# ClickMeter_BlackBox_v1_9_4.net
KiCad netlist of a schematic drawn in EAGLE
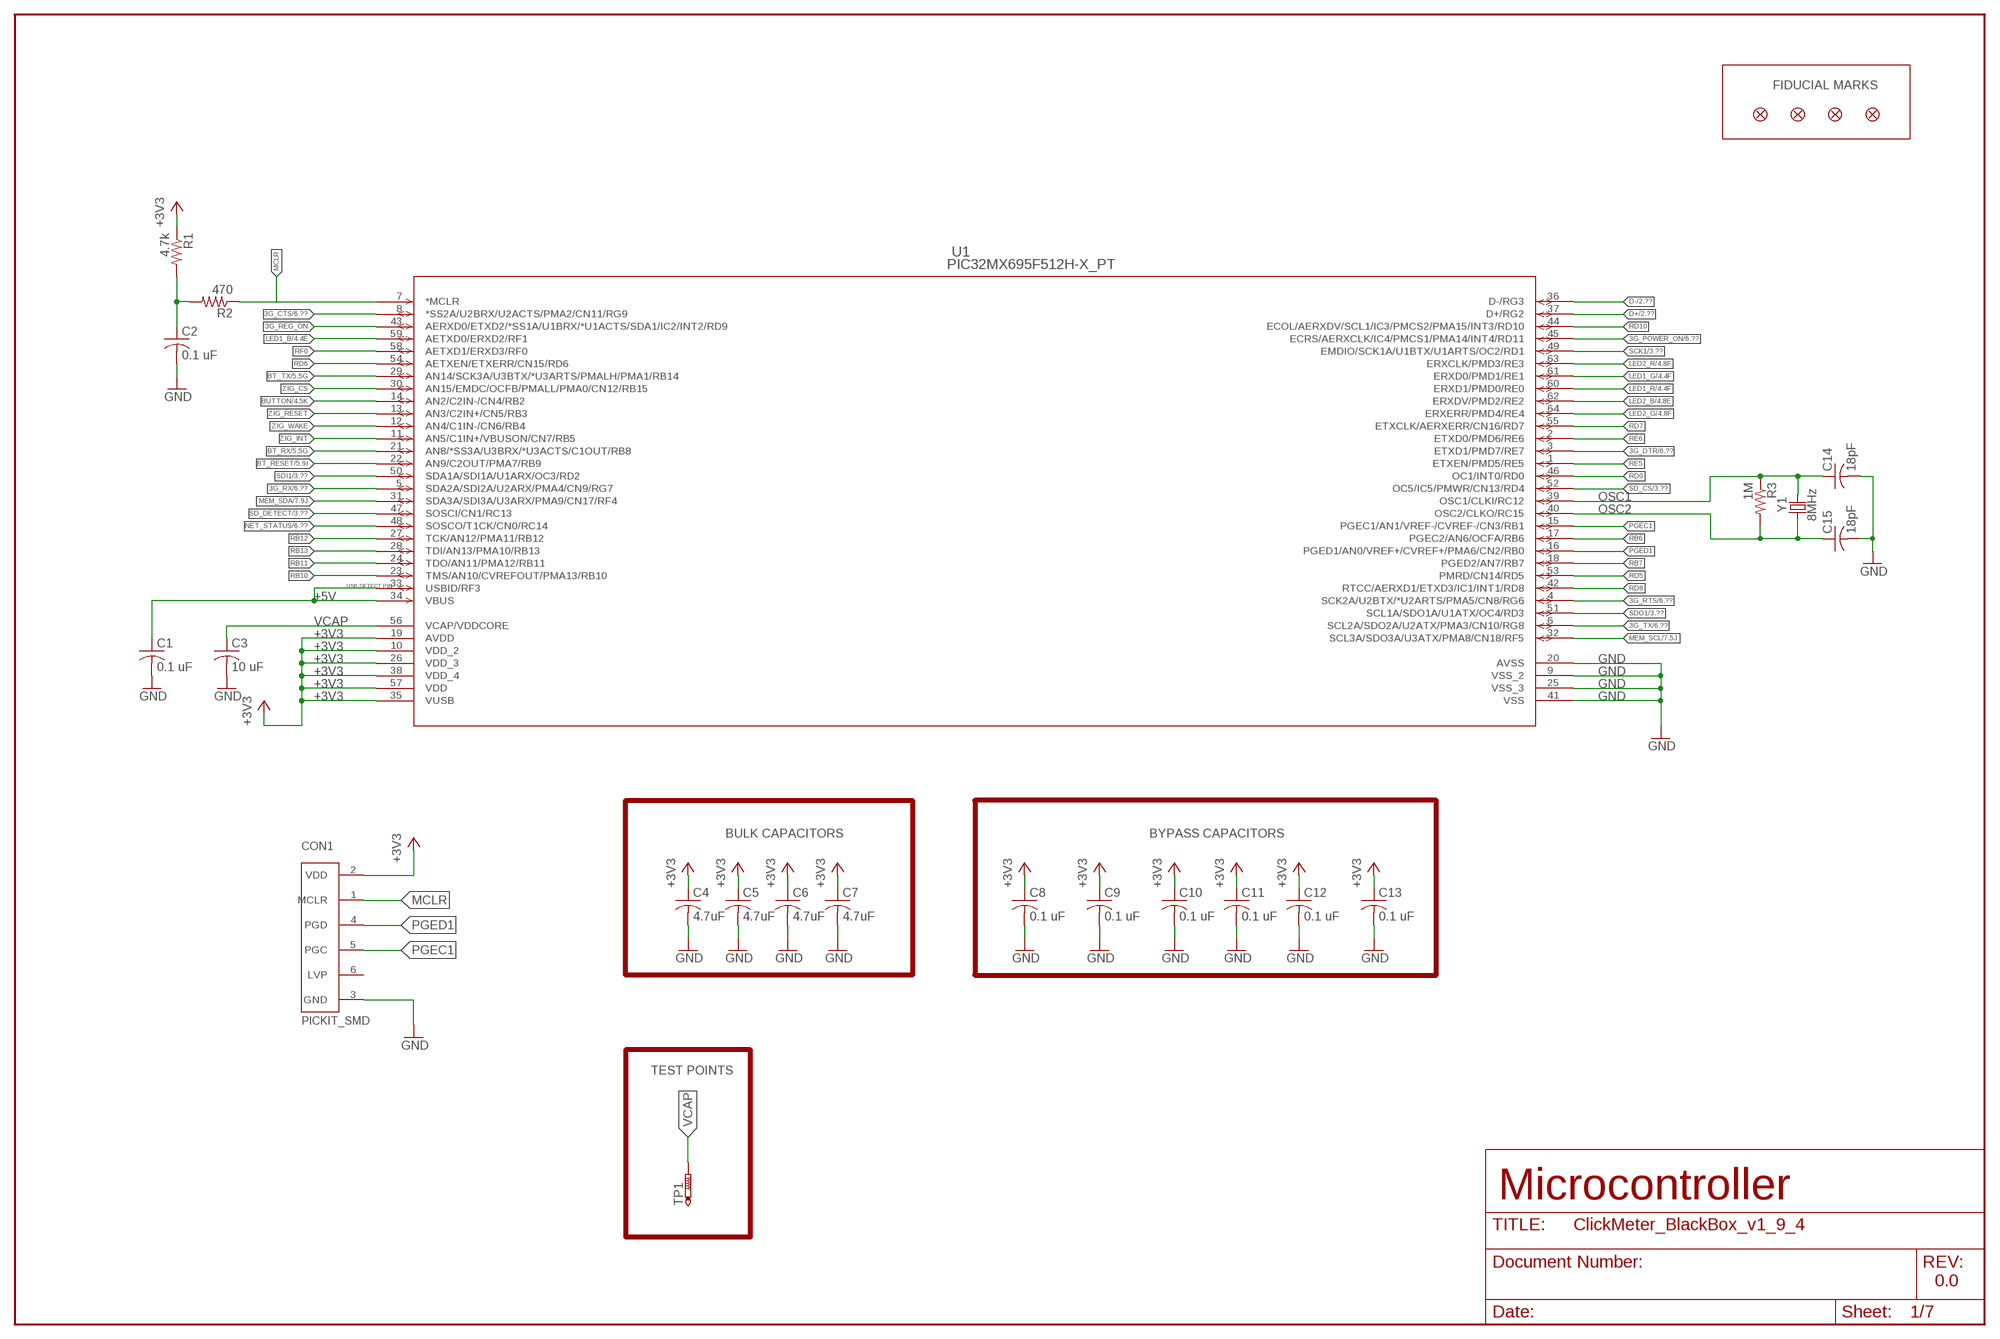
[diagram p0: schematic, sheet 1]
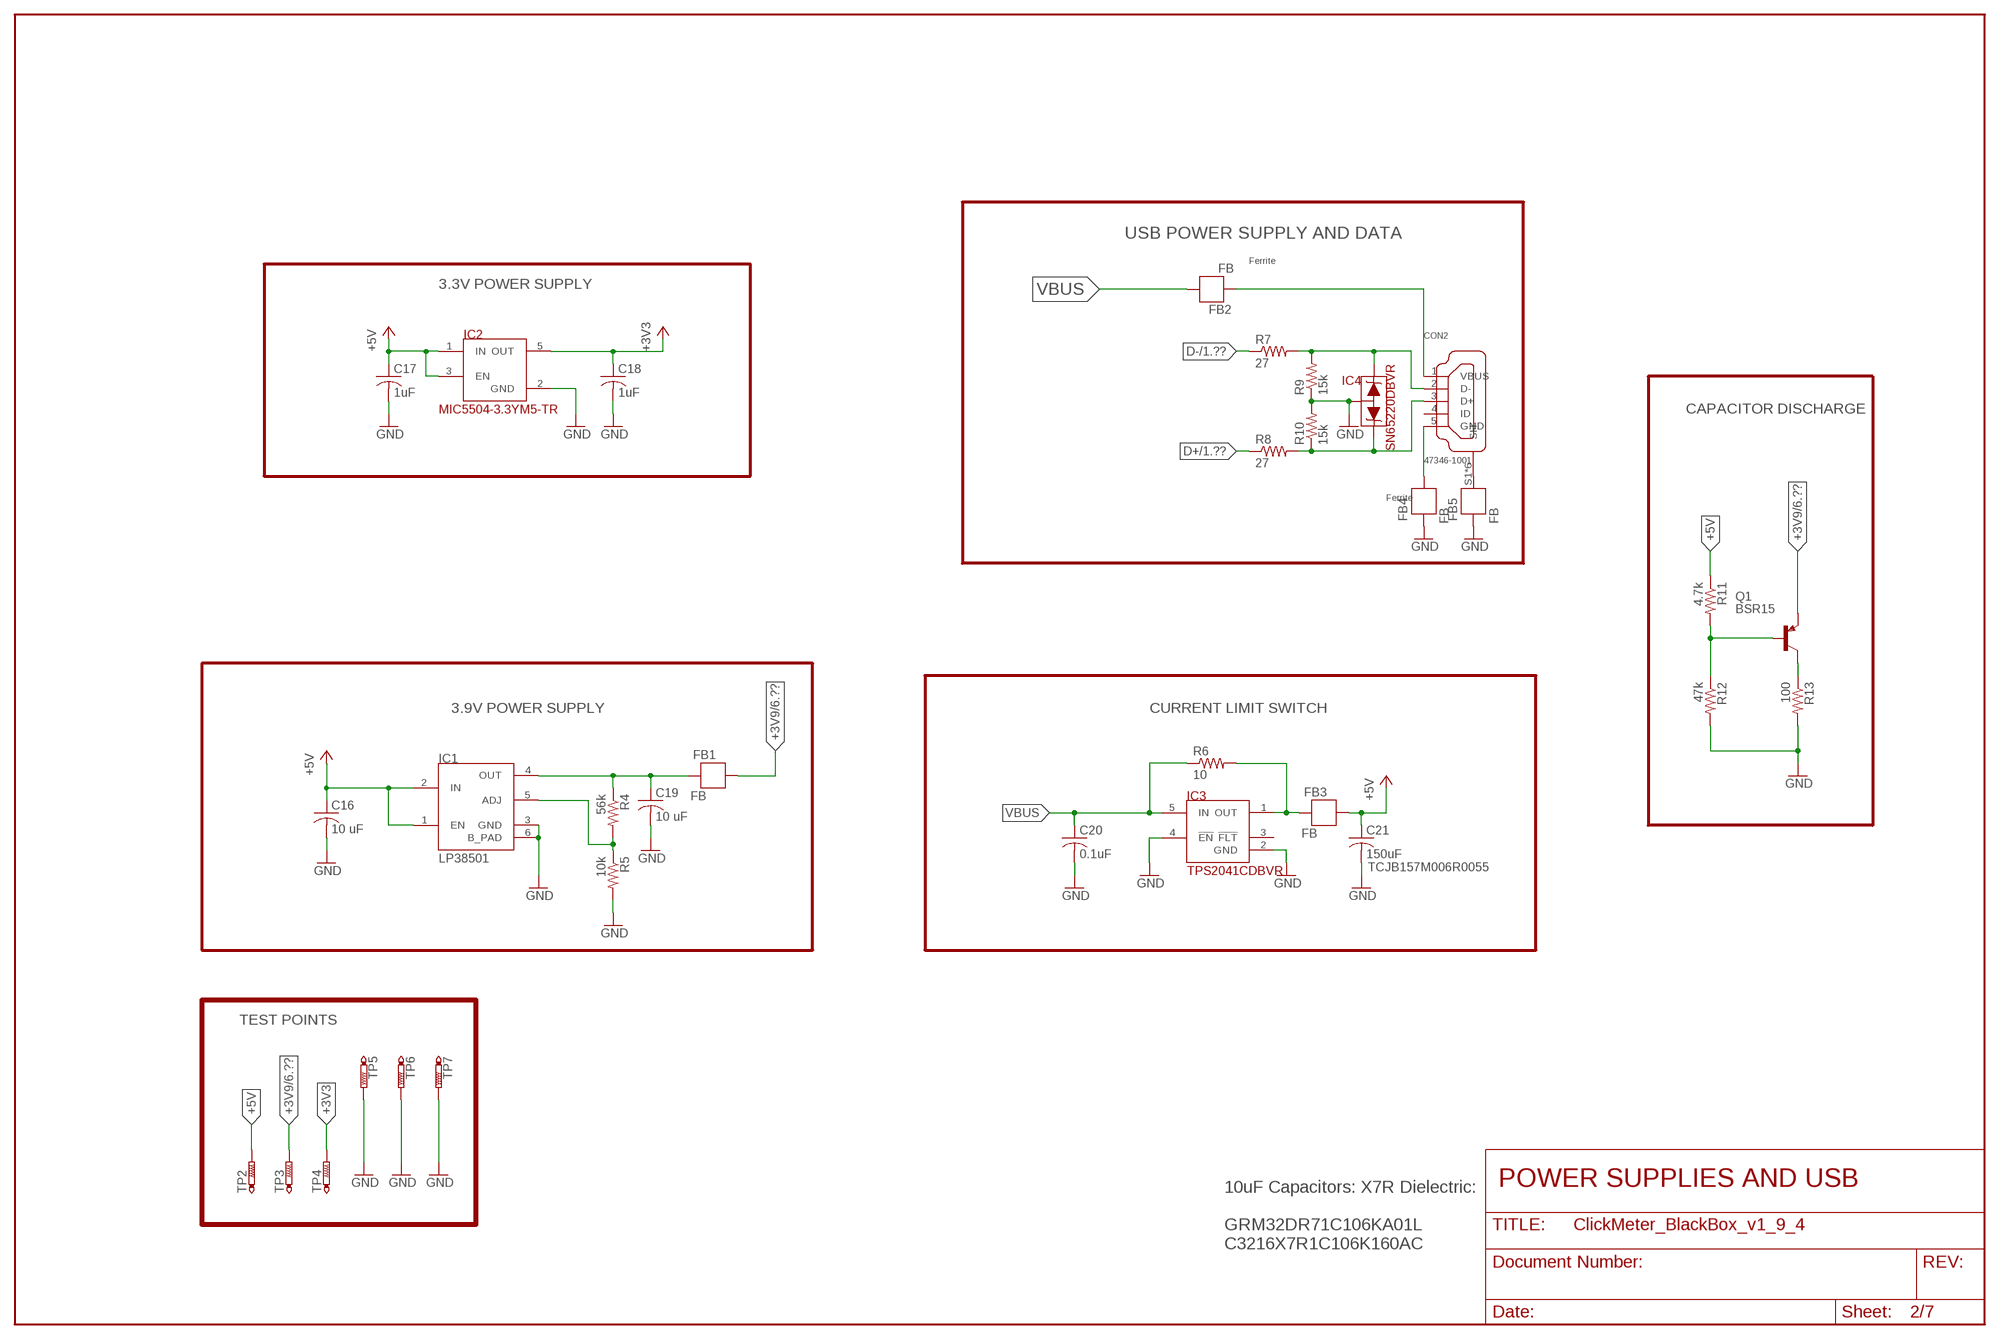
[diagram p1: schematic, sheet 2]
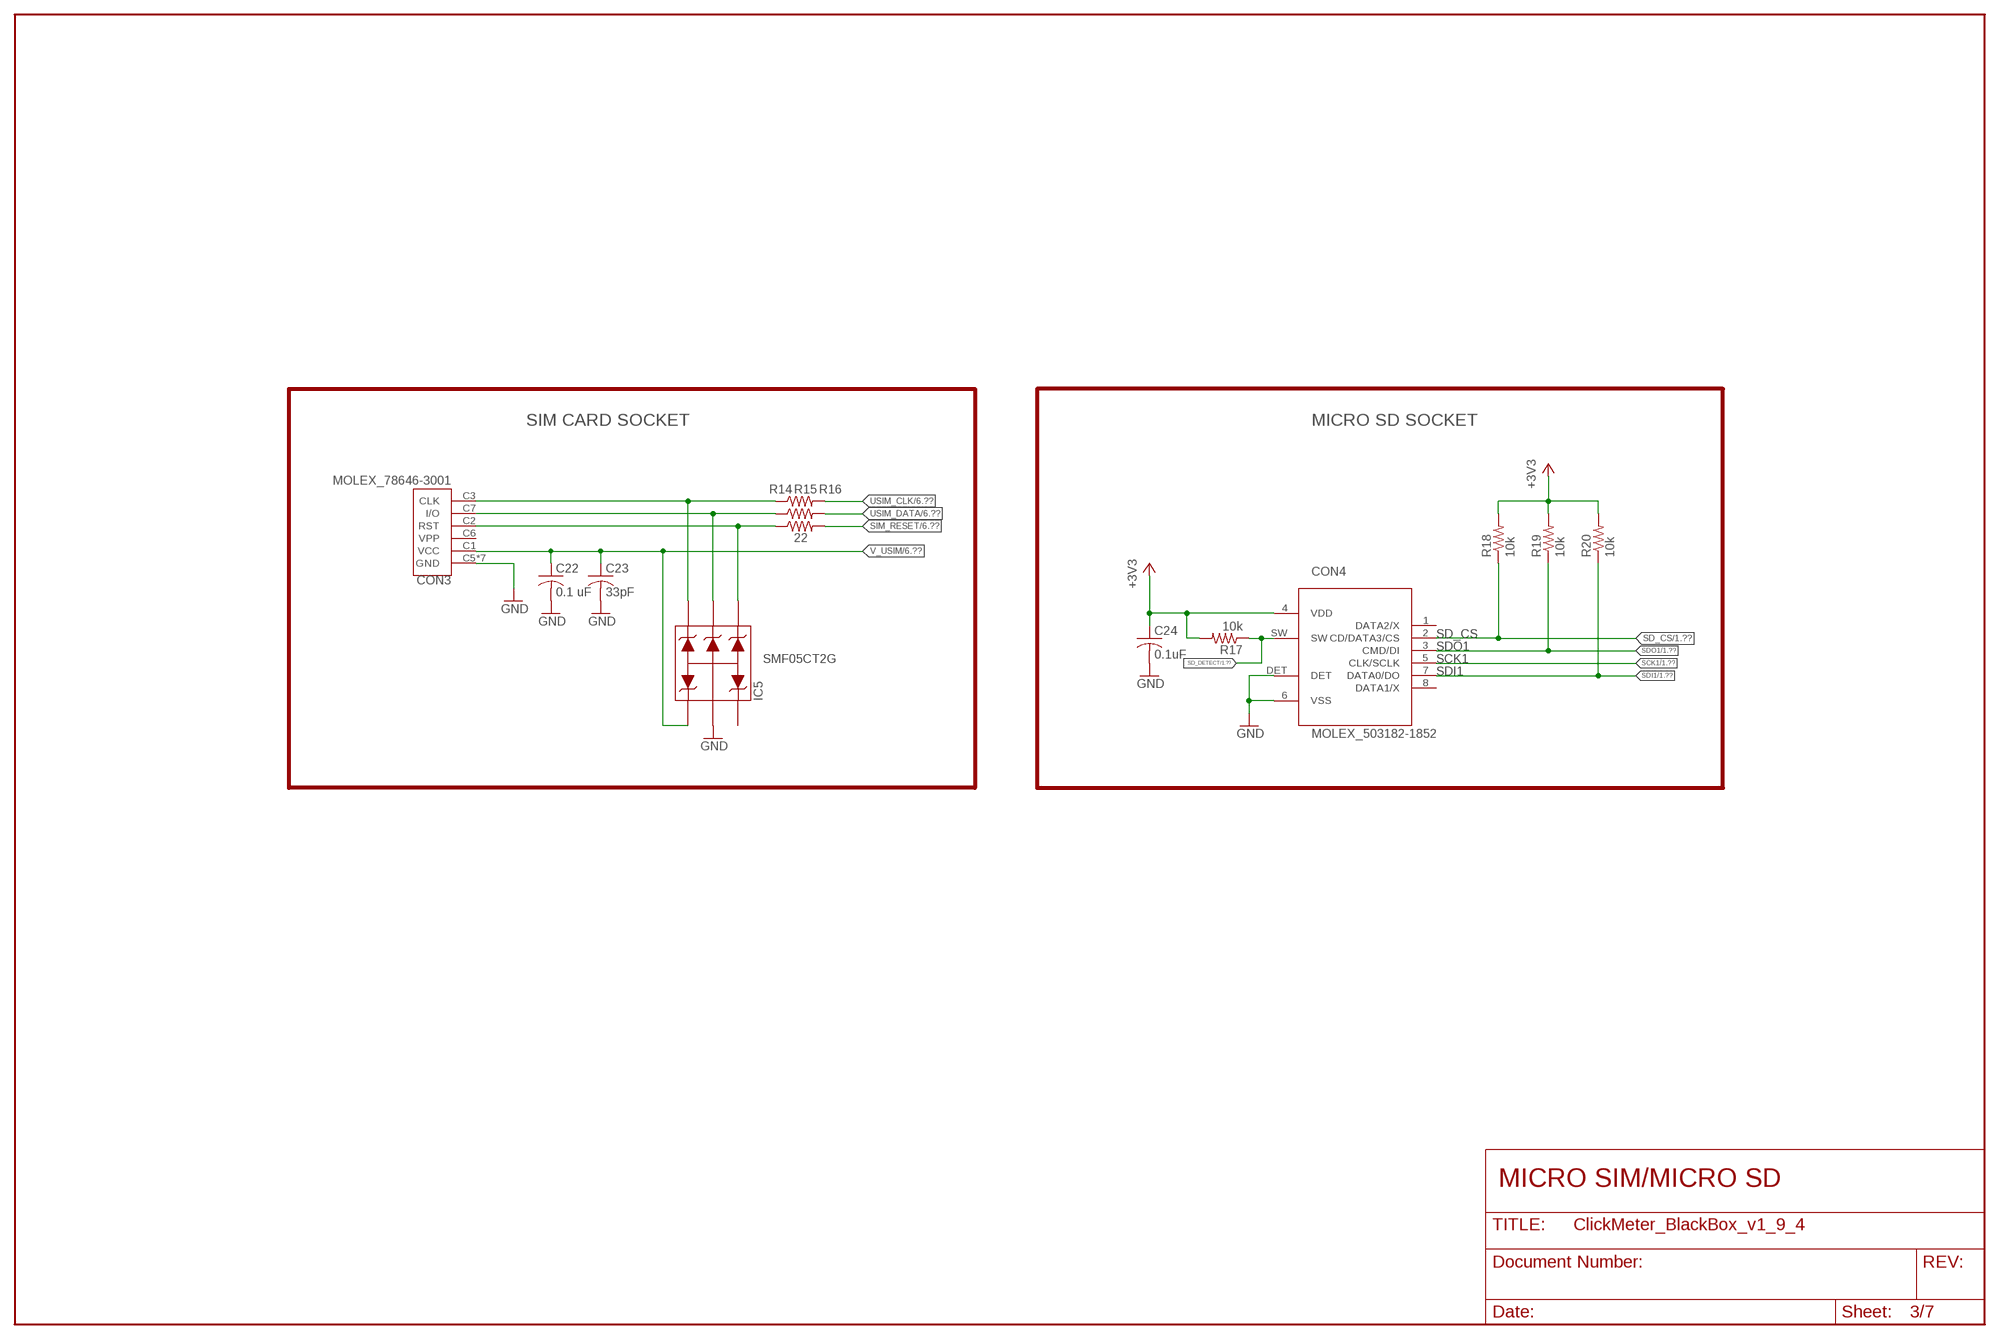
[diagram p2: schematic, sheet 3]
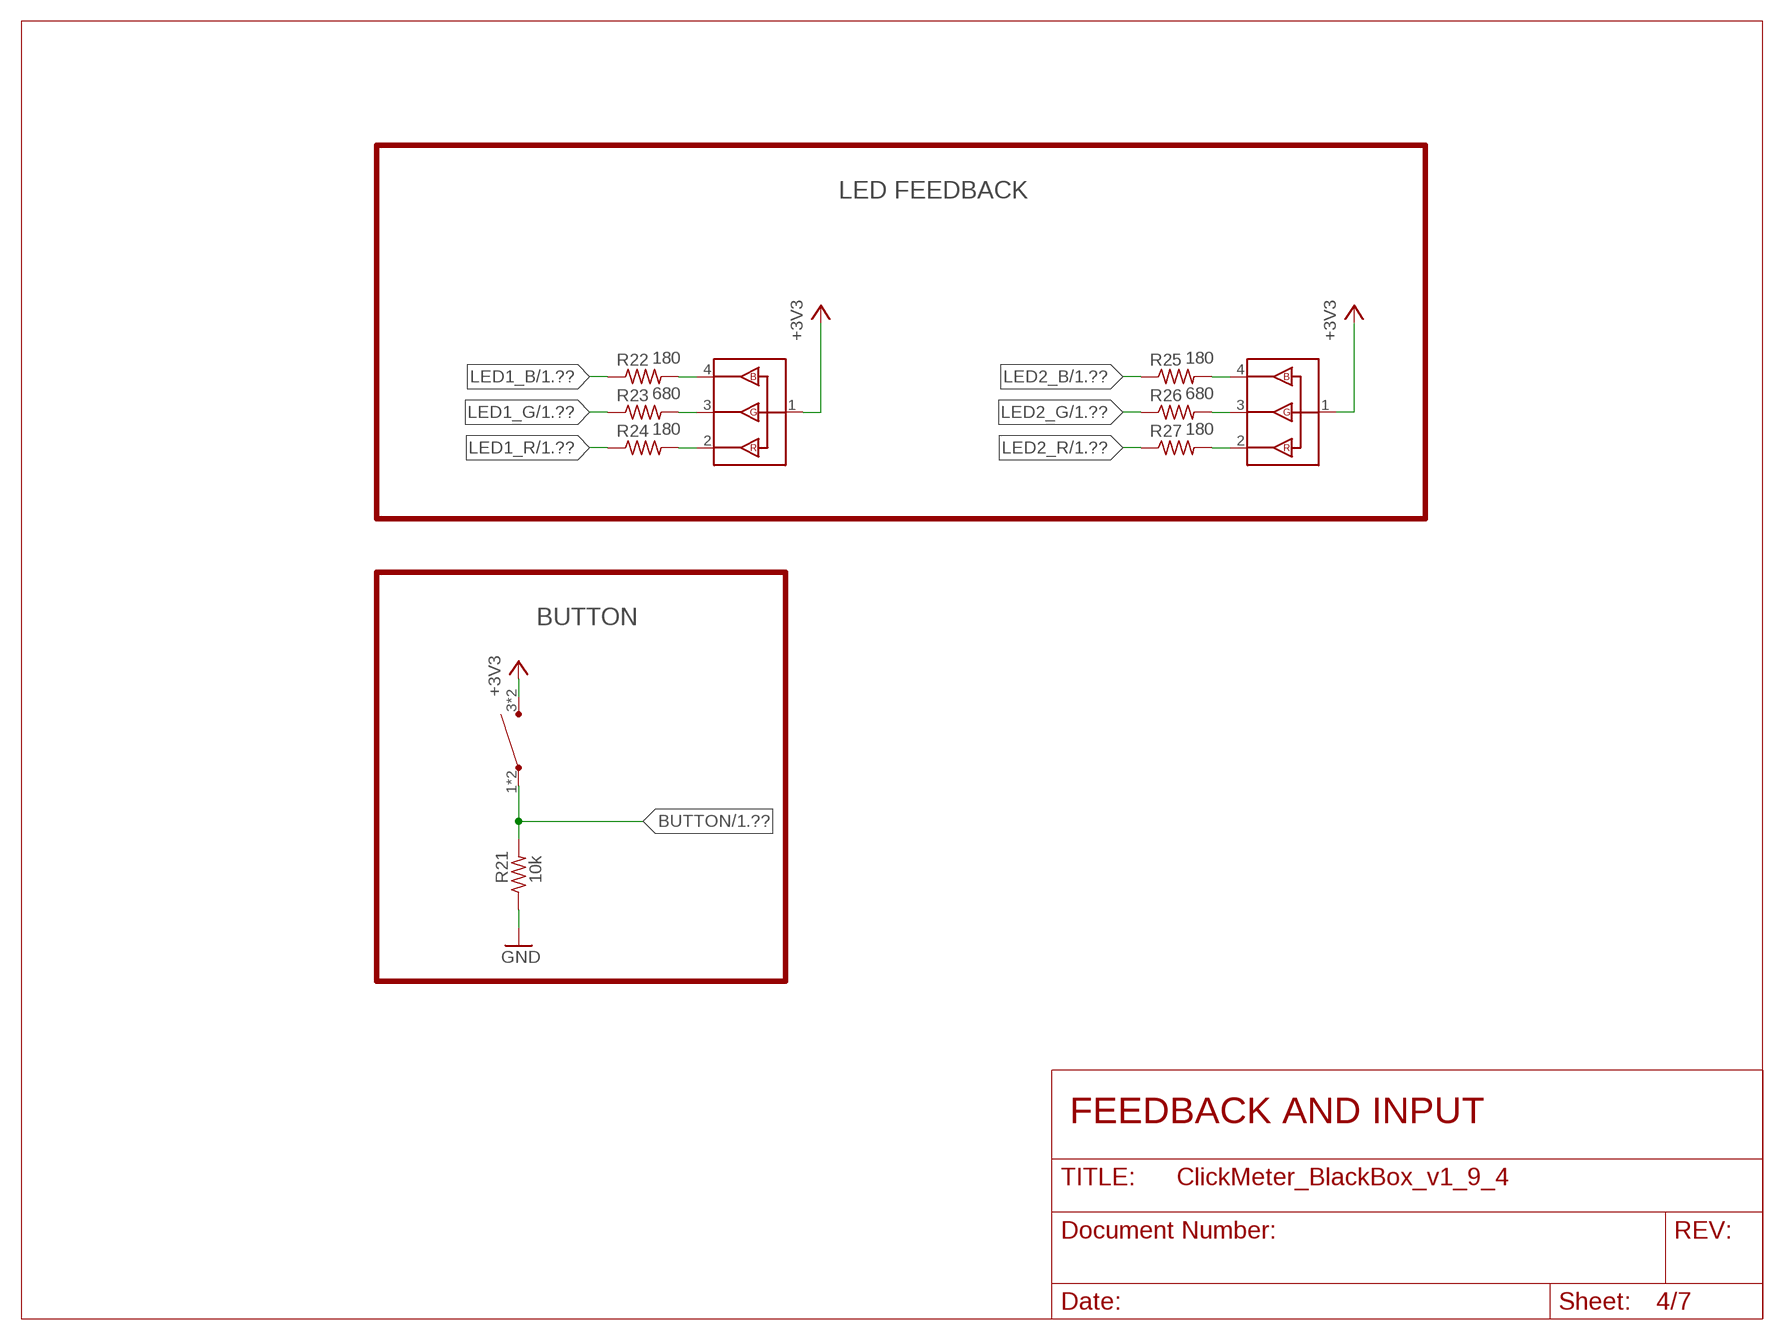
[diagram p3: schematic, sheet 4]
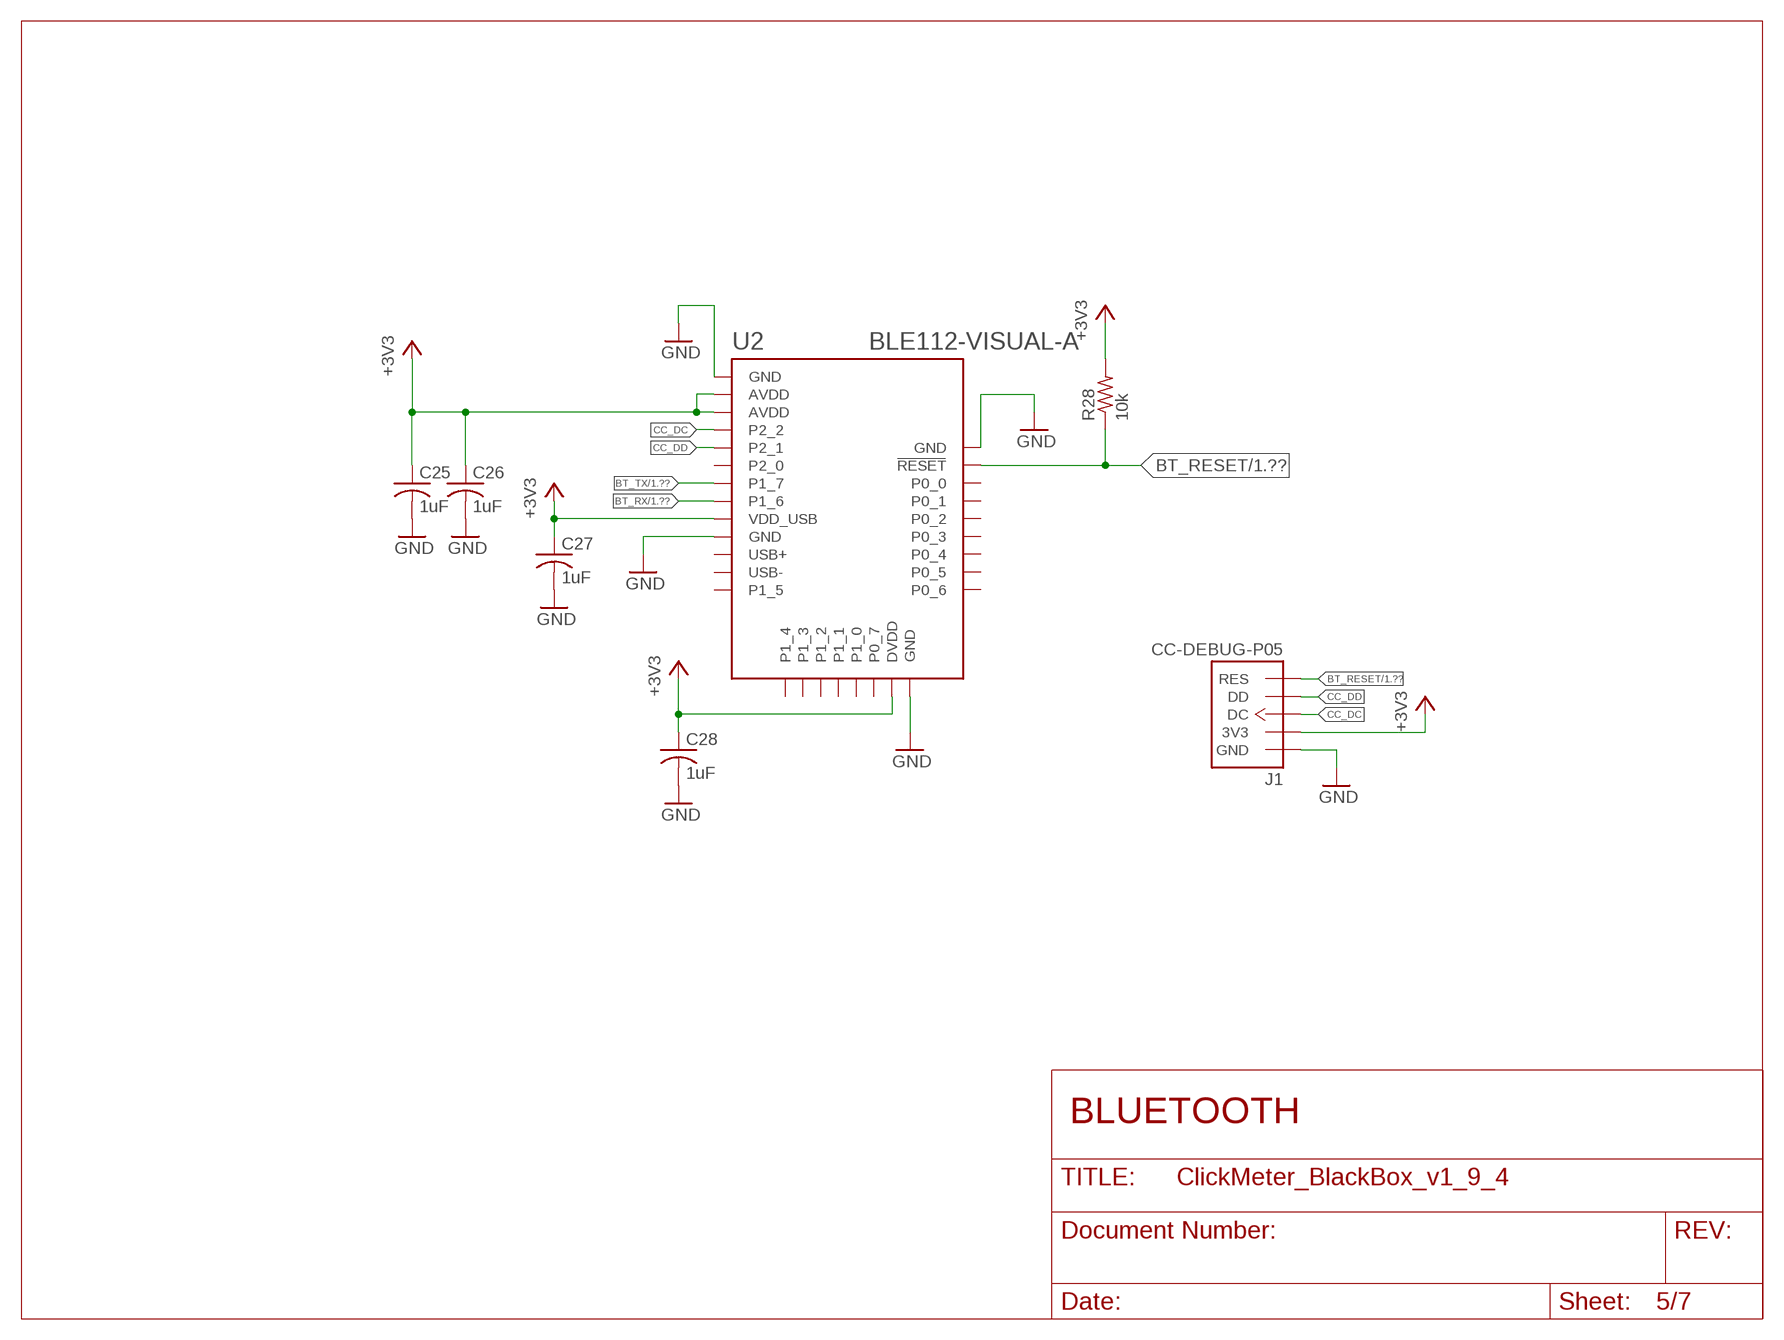
[diagram p4: schematic, sheet 5]
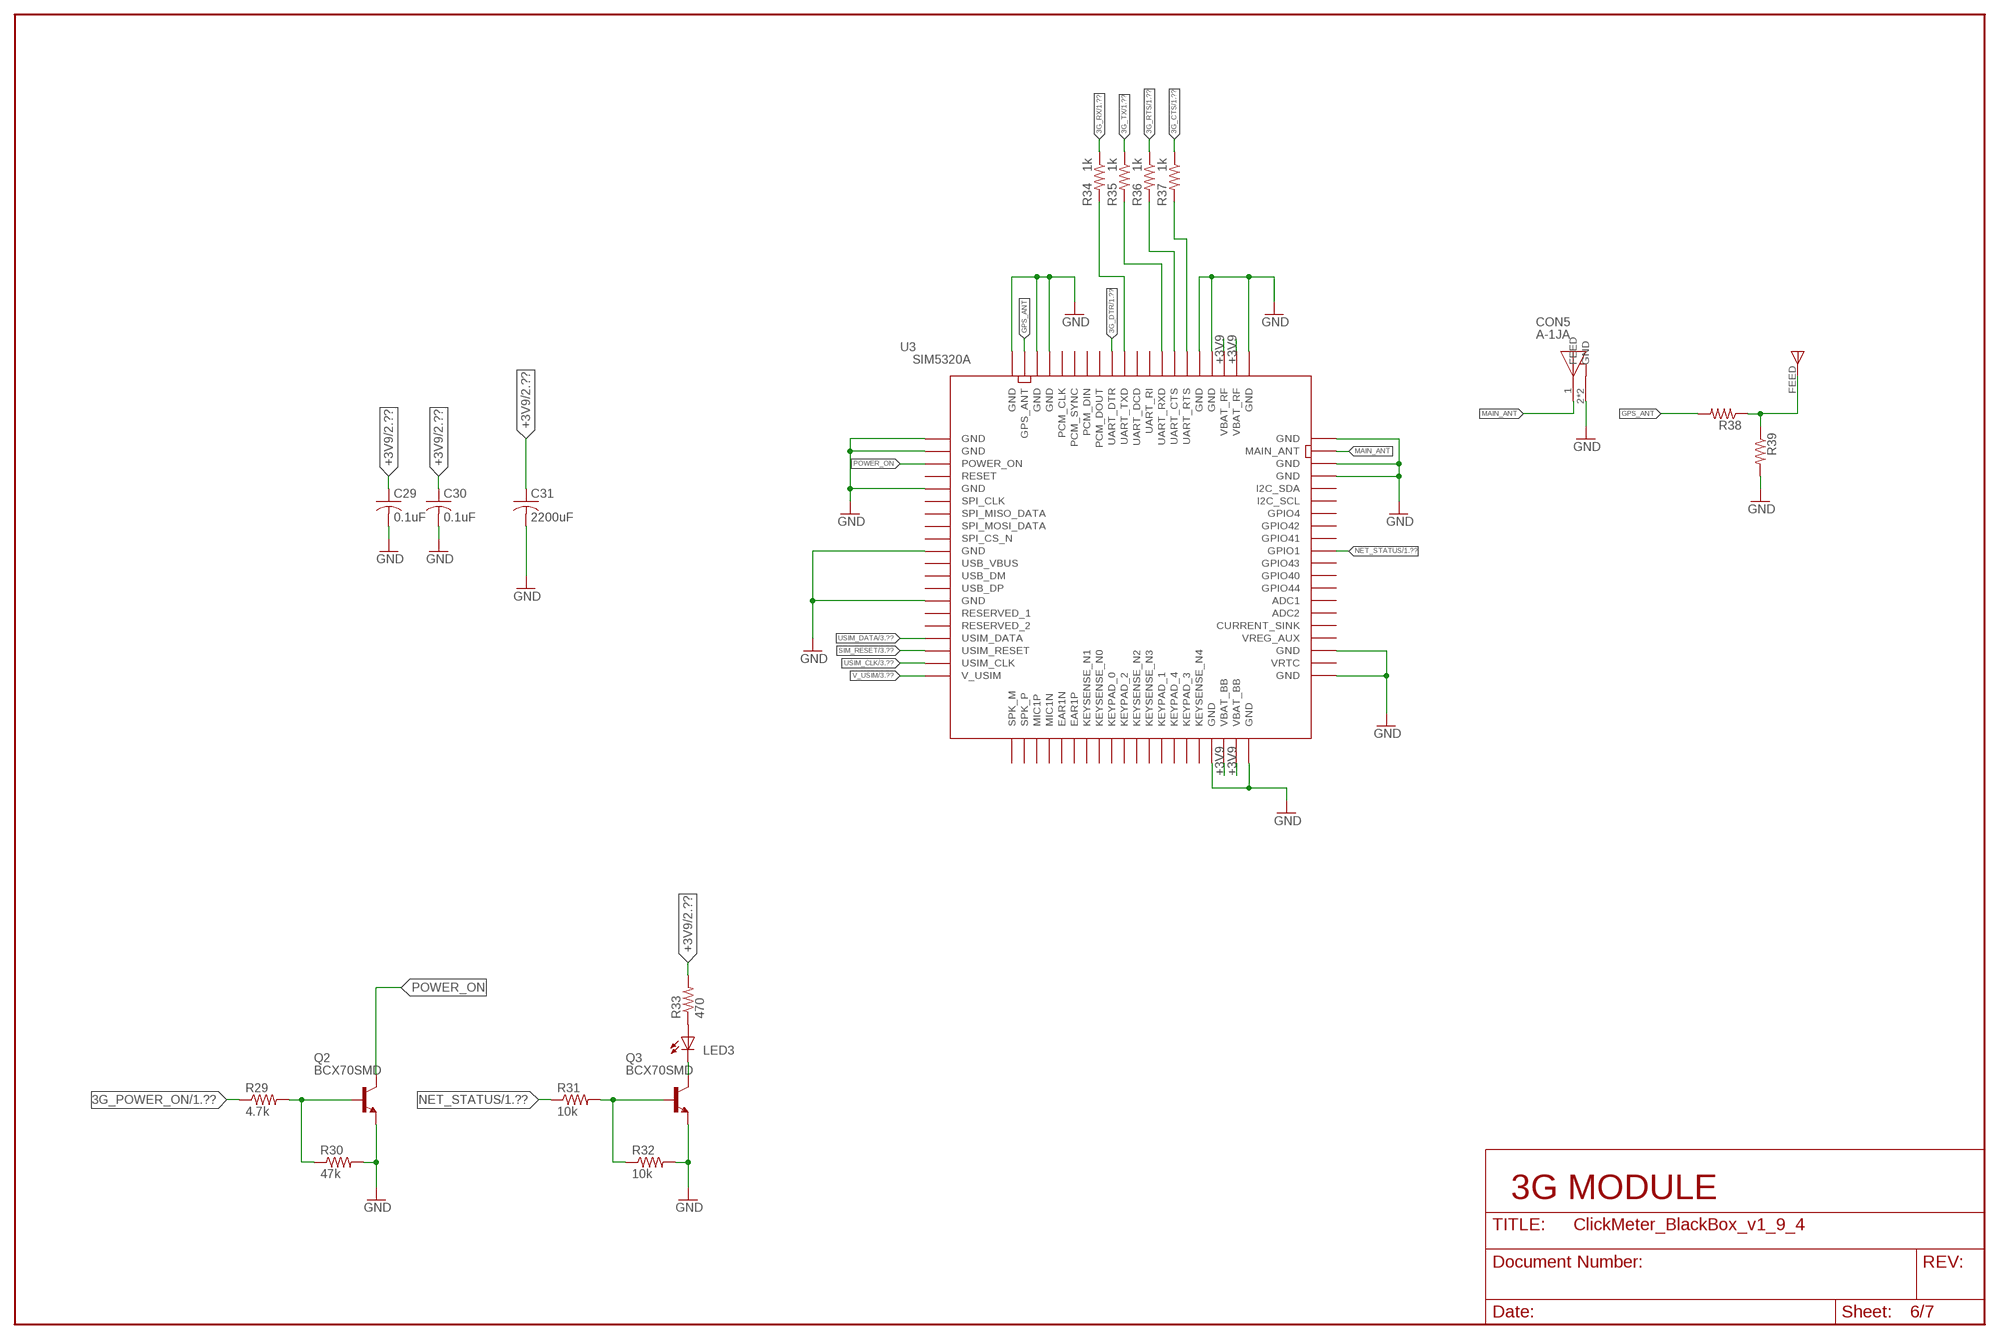
[diagram p5: schematic, sheet 6]
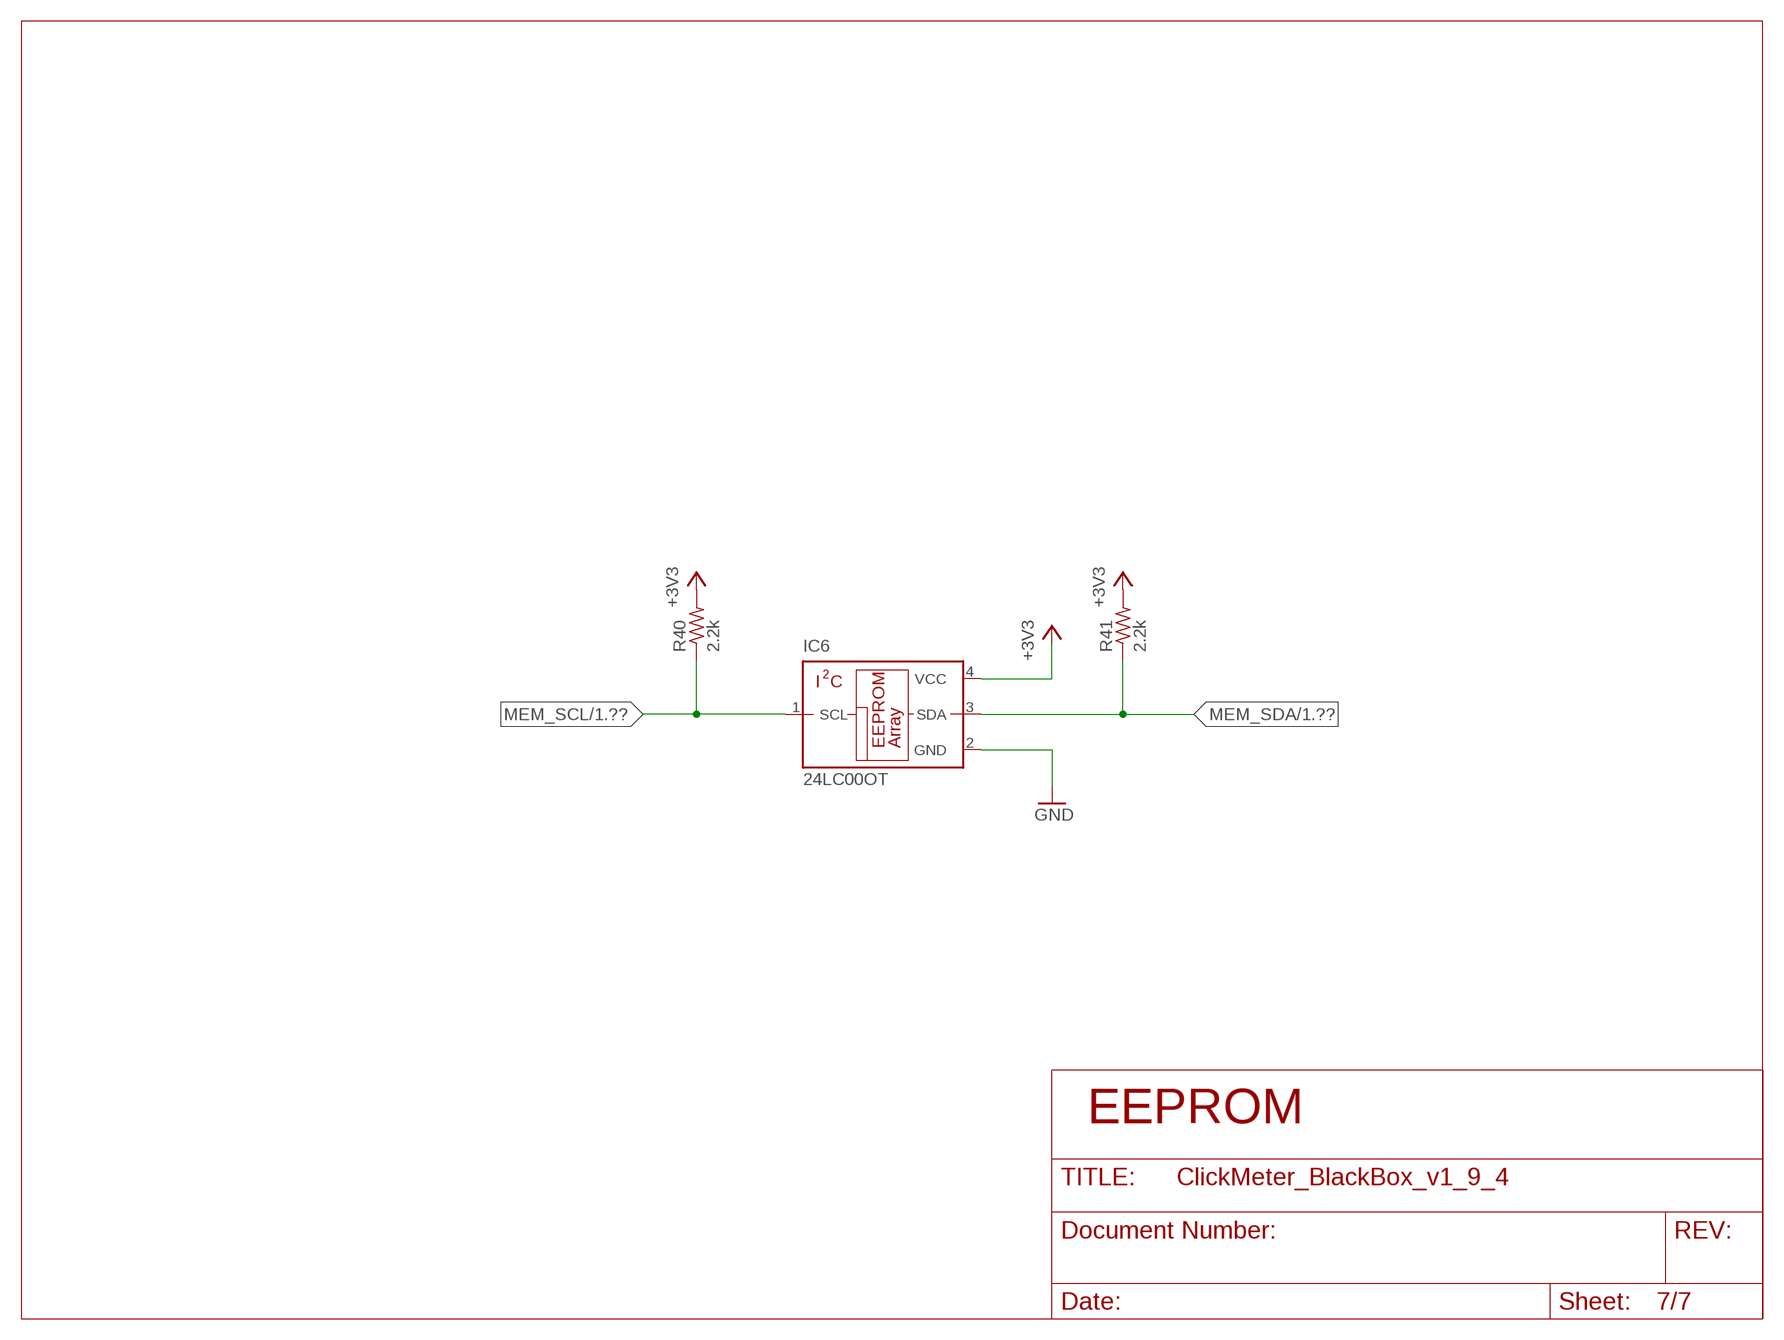
[diagram p6: schematic, sheet 7]

(export (version "E")
  (design (tool "Eeschema 10.0.6"))
  (components
    (comp (ref "C25")
      (value "1uF")
      (footprint "eagle-import:C0603")
      (libsource (lib "eagle-import") (part "C-USC0603"))
    )
    (comp (ref "C26")
      (value "1uF")
      (footprint "eagle-import:C0603")
      (libsource (lib "eagle-import") (part "C-USC0603"))
    )
    (comp (ref "C27")
      (value "1uF")
      (footprint "eagle-import:C0603")
      (libsource (lib "eagle-import") (part "C-USC0603"))
    )
    (comp (ref "C28")
      (value "1uF")
      (footprint "eagle-import:C0603")
      (libsource (lib "eagle-import") (part "C-USC0603"))
    )
    (comp (ref "J1")
      (value "CC-DEBUG-P05")
      (footprint "eagle-import:CC-P05")
      (libsource (lib "eagle-import") (part "CC-DEBUG-P05"))
    )
    (comp (ref "R28")
      (value "10k")
      (footprint "eagle-import:R0603")
      (libsource (lib "eagle-import") (part "R-US_R0603"))
    )
    (comp (ref "U2")
      (value "BLE112-VISUAL-A")
      (footprint "eagle-import:BLE112-A")
      (libsource (lib "eagle-import") (part "BLE112-VISUAL-A"))
    )
    (comp (ref "C16")
      (value "10 uF")
      (footprint "eagle-import:C0805")
      (libsource (lib "eagle-import") (part "C-USC0805"))
    )
    (comp (ref "C17")
      (value "1uF")
      (footprint "eagle-import:C0603")
      (libsource (lib "eagle-import") (part "C-USC0603"))
    )
    (comp (ref "C18")
      (value "1uF")
      (footprint "eagle-import:C0603")
      (libsource (lib "eagle-import") (part "C-USC0603"))
    )
    (comp (ref "C19")
      (value "10 uF")
      (footprint "eagle-import:C0805")
      (libsource (lib "eagle-import") (part "C-USC0805"))
    )
    (comp (ref "C20")
      (value "0.1uF")
      (footprint "eagle-import:C0603")
      (libsource (lib "eagle-import") (part "C-USC0603"))
    )
    (comp (ref "C21")
      (value "150uF")
      (footprint "eagle-import:C1210")
      (libsource (lib "eagle-import") (part "C-USC1210"))
    )
    (comp (ref "CON2")
      (value "47346-1001")
      (footprint "eagle-import:47346-1001")
      (libsource (lib "eagle-import") (part "47346-1001"))
    )
    (comp (ref "FB1")
      (value "FB")
      (footprint "eagle-import:0603")
      (libsource (lib "eagle-import") (part "FB"))
    )
    (comp (ref "FB2")
      (value "FB")
      (footprint "eagle-import:0603")
      (libsource (lib "eagle-import") (part "FB"))
    )
    (comp (ref "FB3")
      (value "FB")
      (footprint "eagle-import:0603")
      (libsource (lib "eagle-import") (part "FB"))
    )
    (comp (ref "FB4")
      (value "FB")
      (footprint "eagle-import:0603")
      (libsource (lib "eagle-import") (part "FB"))
    )
    (comp (ref "FB5")
      (value "FB")
      (footprint "eagle-import:0603")
      (libsource (lib "eagle-import") (part "FB"))
    )
    (comp (ref "IC1")
      (value "LP38501")
      (footprint "eagle-import:TO-263-5")
      (libsource (lib "eagle-import") (part "LP38501"))
    )
    (comp (ref "IC2")
      (value "MIC5504-3.3YM5-TR")
      (footprint "eagle-import:SOT-23-5")
      (libsource (lib "eagle-import") (part "MIC5504-3.3YM5-TR"))
    )
    (comp (ref "IC3")
      (value "TPS2041CDBVR")
      (footprint "eagle-import:SOT-23-5")
      (libsource (lib "eagle-import") (part "TPS2041CDBVR"))
    )
    (comp (ref "IC4")
      (value "SN65220DBVR")
      (footprint "eagle-import:SOT-23-6")
      (libsource (lib "eagle-import") (part "SN65220DBVR"))
    )
    (comp (ref "Q1")
      (value "BSR15")
      (footprint "eagle-import:SOT23")
      (libsource (lib "eagle-import") (part "BSR15"))
    )
    (comp (ref "R4")
      (value "56k")
      (footprint "eagle-import:R0603")
      (libsource (lib "eagle-import") (part "R-US_R0603"))
    )
    (comp (ref "R5")
      (value "10k")
      (footprint "eagle-import:R0603")
      (libsource (lib "eagle-import") (part "R-US_R0603"))
    )
    (comp (ref "R6")
      (value "10")
      (footprint "eagle-import:R2010")
      (libsource (lib "eagle-import") (part "R-US_R2010"))
    )
    (comp (ref "R7")
      (value "27")
      (footprint "eagle-import:R0603")
      (libsource (lib "eagle-import") (part "R-US_R0603"))
    )
    (comp (ref "R8")
      (value "27")
      (footprint "eagle-import:R0603")
      (libsource (lib "eagle-import") (part "R-US_R0603"))
    )
    (comp (ref "R9")
      (value "15k")
      (footprint "eagle-import:R0603")
      (libsource (lib "eagle-import") (part "R-US_R0603"))
    )
    (comp (ref "R10")
      (value "15k")
      (footprint "eagle-import:R0603")
      (libsource (lib "eagle-import") (part "R-US_R0603"))
    )
    (comp (ref "R11")
      (value "4.7k")
      (footprint "eagle-import:R0603")
      (libsource (lib "eagle-import") (part "R-US_R0603"))
    )
    (comp (ref "R12")
      (value "47k")
      (footprint "eagle-import:R0603")
      (libsource (lib "eagle-import") (part "R-US_R0603"))
    )
    (comp (ref "R13")
      (value "100")
      (footprint "eagle-import:R0603")
      (libsource (lib "eagle-import") (part "R-US_R0603"))
    )
    (comp (ref "TP2")
      (value "PTR1B1,27")
      (footprint "eagle-import:B1,27")
      (libsource (lib "eagle-import") (part "PTR1B1,27"))
    )
    (comp (ref "TP3")
      (value "PTR1B1,27")
      (footprint "eagle-import:B1,27")
      (libsource (lib "eagle-import") (part "PTR1B1,27"))
    )
    (comp (ref "TP4")
      (value "PTR1B1,27")
      (footprint "eagle-import:B1,27")
      (libsource (lib "eagle-import") (part "PTR1B1,27"))
    )
    (comp (ref "TP5")
      (value "PTR1B1,27")
      (footprint "eagle-import:B1,27")
      (libsource (lib "eagle-import") (part "PTR1B1,27"))
    )
    (comp (ref "TP6")
      (value "PTR1B1,27")
      (footprint "eagle-import:B1,27")
      (libsource (lib "eagle-import") (part "PTR1B1,27"))
    )
    (comp (ref "TP7")
      (value "PTR1B1,27")
      (footprint "eagle-import:B1,27")
      (libsource (lib "eagle-import") (part "PTR1B1,27"))
    )
    (comp (ref "ANT1")
      (value "1575AT43A0040E")
      (footprint "eagle-import:1575AT43A0040E")
      (libsource (lib "eagle-import") (part "1575AT43A0040E"))
    )
    (comp (ref "C29")
      (value "0.1uF")
      (footprint "eagle-import:C0603")
      (libsource (lib "eagle-import") (part "C-USC0603"))
    )
    (comp (ref "C30")
      (value "0.1uF")
      (footprint "eagle-import:C0603")
      (libsource (lib "eagle-import") (part "C-USC0603"))
    )
    (comp (ref "C31")
      (value "2200uF")
      (footprint "eagle-import:592D-2200")
      (libsource (lib "eagle-import") (part "C-USTANTALUM-592D"))
    )
    (comp (ref "CON5")
      (value "A-1JA")
      (footprint "eagle-import:A-1JA")
      (libsource (lib "eagle-import") (part "A-1JA"))
    )
    (comp (ref "LED3")
      (value "LED_ESML0603")
      (footprint "eagle-import:LED_SML0603")
      (libsource (lib "eagle-import") (part "LED_ESML0603"))
    )
    (comp (ref "Q2")
      (value "BCX70SMD")
      (footprint "eagle-import:SOT23")
      (libsource (lib "eagle-import") (part "BCX70SMD"))
    )
    (comp (ref "Q3")
      (value "BCX70SMD")
      (footprint "eagle-import:SOT23")
      (libsource (lib "eagle-import") (part "BCX70SMD"))
    )
    (comp (ref "R29")
      (value "4.7k")
      (footprint "eagle-import:R0603")
      (libsource (lib "eagle-import") (part "R-US_R0603"))
    )
    (comp (ref "R30")
      (value "47k")
      (footprint "eagle-import:R0603")
      (libsource (lib "eagle-import") (part "R-US_R0603"))
    )
    (comp (ref "R31")
      (value "10k")
      (footprint "eagle-import:R0603")
      (libsource (lib "eagle-import") (part "R-US_R0603"))
    )
    (comp (ref "R32")
      (value "10k")
      (footprint "eagle-import:R0603")
      (libsource (lib "eagle-import") (part "R-US_R0603"))
    )
    (comp (ref "R33")
      (value "470")
      (footprint "eagle-import:R0603")
      (libsource (lib "eagle-import") (part "R-US_R0603"))
    )
    (comp (ref "R34")
      (value "1k")
      (footprint "eagle-import:R0402")
      (libsource (lib "eagle-import") (part "R-US_R0402"))
    )
    (comp (ref "R35")
      (value "1k")
      (footprint "eagle-import:R0402")
      (libsource (lib "eagle-import") (part "R-US_R0402"))
    )
    (comp (ref "R36")
      (value "1k")
      (footprint "eagle-import:R0402")
      (libsource (lib "eagle-import") (part "R-US_R0402"))
    )
    (comp (ref "R37")
      (value "1k")
      (footprint "eagle-import:R0402")
      (libsource (lib "eagle-import") (part "R-US_R0402"))
    )
    (comp (ref "R38")
      (value "R-US_R0402")
      (footprint "eagle-import:R0402")
      (libsource (lib "eagle-import") (part "R-US_R0402"))
    )
    (comp (ref "R39")
      (value "R-US_R0402")
      (footprint "eagle-import:R0402")
      (libsource (lib "eagle-import") (part "R-US_R0402"))
    )
    (comp (ref "U3")
      (value "SIM5320A")
      (footprint "eagle-import:SIM5320A")
      (libsource (lib "eagle-import") (part "SIM5320A"))
    )
    (comp (ref "BT1")
      (value "PTS525_SM15")
      (footprint "eagle-import:PTS525SM15SMTR2")
      (libsource (lib "eagle-import") (part "PTS525_SM15"))
    )
    (comp (ref "LED1")
      (value "APTF1616SEEZGQBDC")
      (footprint "eagle-import:APTF1616SEEZGQBDC")
      (libsource (lib "eagle-import") (part "APTF1616SEEZGQBDC"))
    )
    (comp (ref "LED2")
      (value "APTF1616SEEZGQBDC")
      (footprint "eagle-import:APTF1616SEEZGQBDC")
      (libsource (lib "eagle-import") (part "APTF1616SEEZGQBDC"))
    )
    (comp (ref "R21")
      (value "10k")
      (footprint "eagle-import:R0603")
      (libsource (lib "eagle-import") (part "R-US_R0603"))
    )
    (comp (ref "R22")
      (value "180")
      (footprint "eagle-import:R0603")
      (libsource (lib "eagle-import") (part "R-US_R0603"))
    )
    (comp (ref "R23")
      (value "680")
      (footprint "eagle-import:R0603")
      (libsource (lib "eagle-import") (part "R-US_R0603"))
    )
    (comp (ref "R24")
      (value "180")
      (footprint "eagle-import:R0603")
      (libsource (lib "eagle-import") (part "R-US_R0603"))
    )
    (comp (ref "R25")
      (value "180")
      (footprint "eagle-import:R0603")
      (libsource (lib "eagle-import") (part "R-US_R0603"))
    )
    (comp (ref "R26")
      (value "680")
      (footprint "eagle-import:R0603")
      (libsource (lib "eagle-import") (part "R-US_R0603"))
    )
    (comp (ref "R27")
      (value "180")
      (footprint "eagle-import:R0603")
      (libsource (lib "eagle-import") (part "R-US_R0603"))
    )
    (comp (ref "IC6")
      (value "24LC00OT")
      (footprint "eagle-import:SOT23-5L")
      (fields (field (name "MF") "MICROCHIP") (field (name "MPN") "24LC00T-I/OT"))
      (libsource (lib "eagle-import") (part "2400OTLC"))
    )
    (comp (ref "R40")
      (value "2.2k")
      (footprint "eagle-import:R0603")
      (libsource (lib "eagle-import") (part "R-US_R0603"))
    )
    (comp (ref "R41")
      (value "2.2k")
      (footprint "eagle-import:R0603")
      (libsource (lib "eagle-import") (part "R-US_R0603"))
    )
    (comp (ref "C1")
      (value "0.1 uF")
      (footprint "eagle-import:C0603")
      (libsource (lib "eagle-import") (part "C-USC0603"))
    )
    (comp (ref "C2")
      (value "0.1 uF")
      (footprint "eagle-import:C0603")
      (libsource (lib "eagle-import") (part "C-USC0603"))
    )
    (comp (ref "C3")
      (value "10 uF")
      (footprint "eagle-import:C0805")
      (libsource (lib "eagle-import") (part "C-USC0805"))
    )
    (comp (ref "C4")
      (value "4.7uF")
      (footprint "eagle-import:C0603")
      (libsource (lib "eagle-import") (part "C-USC0603"))
    )
    (comp (ref "C5")
      (value "4.7uF")
      (footprint "eagle-import:C0603")
      (libsource (lib "eagle-import") (part "C-USC0603"))
    )
    (comp (ref "C6")
      (value "4.7uF")
      (footprint "eagle-import:C0603")
      (libsource (lib "eagle-import") (part "C-USC0603"))
    )
    (comp (ref "C7")
      (value "4.7uF")
      (footprint "eagle-import:C0603")
      (libsource (lib "eagle-import") (part "C-USC0603"))
    )
    (comp (ref "C8")
      (value "0.1 uF")
      (footprint "eagle-import:C0603")
      (libsource (lib "eagle-import") (part "C-USC0603"))
    )
    (comp (ref "C9")
      (value "0.1 uF")
      (footprint "eagle-import:C0603")
      (libsource (lib "eagle-import") (part "C-USC0603"))
    )
    (comp (ref "C10")
      (value "0.1 uF")
      (footprint "eagle-import:C0603")
      (libsource (lib "eagle-import") (part "C-USC0603"))
    )
    (comp (ref "C11")
      (value "0.1 uF")
      (footprint "eagle-import:C0603")
      (libsource (lib "eagle-import") (part "C-USC0603"))
    )
    (comp (ref "C12")
      (value "0.1 uF")
      (footprint "eagle-import:C0603")
      (libsource (lib "eagle-import") (part "C-USC0603"))
    )
    (comp (ref "C13")
      (value "0.1 uF")
      (footprint "eagle-import:C0603")
      (libsource (lib "eagle-import") (part "C-USC0603"))
    )
    (comp (ref "C14")
      (value "18pF")
      (footprint "eagle-import:C0603")
      (libsource (lib "eagle-import") (part "C-USC0603"))
    )
    (comp (ref "C15")
      (value "18pF")
      (footprint "eagle-import:C0603")
      (libsource (lib "eagle-import") (part "C-USC0603"))
    )
    (comp (ref "CON1")
      (value "PICKIT_SMD")
      (footprint "eagle-import:SMD_PICKIT")
      (libsource (lib "eagle-import") (part "PICKIT_SMD"))
    )
    (comp (ref "F1")
      (value "FIDUCIAL")
      (footprint "eagle-import:FIDUCIAL")
      (libsource (lib "eagle-import") (part "FIDUCIAL"))
    )
    (comp (ref "F2")
      (value "FIDUCIAL")
      (footprint "eagle-import:FIDUCIAL")
      (libsource (lib "eagle-import") (part "FIDUCIAL"))
    )
    (comp (ref "F3")
      (value "FIDUCIAL")
      (footprint "eagle-import:FIDUCIAL")
      (libsource (lib "eagle-import") (part "FIDUCIAL"))
    )
    (comp (ref "F4")
      (value "FIDUCIAL")
      (footprint "eagle-import:FIDUCIAL")
      (libsource (lib "eagle-import") (part "FIDUCIAL"))
    )
    (comp (ref "R1")
      (value "4.7k")
      (footprint "eagle-import:R0603")
      (libsource (lib "eagle-import") (part "R-US_R0603"))
    )
    (comp (ref "R2")
      (value "470")
      (footprint "eagle-import:R0603")
      (libsource (lib "eagle-import") (part "R-US_R0603"))
    )
    (comp (ref "R3")
      (value "1M")
      (footprint "eagle-import:R0603")
      (libsource (lib "eagle-import") (part "R-US_R0603"))
    )
    (comp (ref "TP1")
      (value "PTR1B1,27")
      (footprint "eagle-import:B1,27")
      (libsource (lib "eagle-import") (part "PTR1B1,27"))
    )
    (comp (ref "U1")
      (value "PIC32MX695F512H-X_PT")
      (footprint "eagle-import:TQFP64_10X10MC")
      (libsource (lib "eagle-import") (part "PIC32MX695F512H-X_PT"))
    )
    (comp (ref "Y1")
      (value "8MHz")
      (footprint "eagle-import:CRYSTAL-TXC-7A")
      (libsource (lib "eagle-import") (part "CRYSTALTXC-7A"))
    )
    (comp (ref "C22")
      (value "0.1 uF")
      (footprint "eagle-import:C0603")
      (libsource (lib "eagle-import") (part "C-USC0603"))
    )
    (comp (ref "C23")
      (value "33pF")
      (footprint "eagle-import:C0603")
      (libsource (lib "eagle-import") (part "C-USC0603"))
    )
    (comp (ref "C24")
      (value "0.1uF")
      (footprint "eagle-import:C0603")
      (libsource (lib "eagle-import") (part "C-USC0603"))
    )
    (comp (ref "CON3")
      (value "MOLEX_78646-3001")
      (footprint "eagle-import:MOLEX_78646-3001")
      (libsource (lib "eagle-import") (part "MOLEX_78646-3001"))
    )
    (comp (ref "CON4")
      (value "MOLEX_503182-1852")
      (footprint "eagle-import:MOLEX_503182-1852")
      (libsource (lib "eagle-import") (part "MOLEX_503182-1852"))
    )
    (comp (ref "IC5")
      (value "SMF05CT2G")
      (footprint "eagle-import:SC-88_SC70-6_SOT-363")
      (libsource (lib "eagle-import") (part "SMF05CT2G"))
    )
    (comp (ref "R14")
      (value "22")
      (footprint "eagle-import:R0603")
      (libsource (lib "eagle-import") (part "R-US_R0603"))
    )
    (comp (ref "R15")
      (value "22")
      (footprint "eagle-import:R0603")
      (libsource (lib "eagle-import") (part "R-US_R0603"))
    )
    (comp (ref "R16")
      (value "22")
      (footprint "eagle-import:R0603")
      (libsource (lib "eagle-import") (part "R-US_R0603"))
    )
    (comp (ref "R17")
      (value "10k")
      (footprint "eagle-import:R0603")
      (libsource (lib "eagle-import") (part "R-US_R0603"))
    )
    (comp (ref "R18")
      (value "10k")
      (footprint "eagle-import:R0603")
      (libsource (lib "eagle-import") (part "R-US_R0603"))
    )
    (comp (ref "R19")
      (value "10k")
      (footprint "eagle-import:R0603")
      (libsource (lib "eagle-import") (part "R-US_R0603"))
    )
    (comp (ref "R20")
      (value "10k")
      (footprint "eagle-import:R0603")
      (libsource (lib "eagle-import") (part "R-US_R0603"))
    )
  )
  (nets
    (net (code "1") (name "+3V3") (class "Default")
      (node (ref "BT1") (pin "3") (pinfunction "P$2_3") (pintype "bidirectional"))
      (node (ref "BT1") (pin "4") (pinfunction "P$2_4") (pintype "bidirectional"))
      (node (ref "C10") (pin "1") (pinfunction "1_1") (pintype "passive"))
      (node (ref "C11") (pin "1") (pinfunction "1_1") (pintype "passive"))
      (node (ref "C12") (pin "1") (pinfunction "1_1") (pintype "passive"))
      (node (ref "C13") (pin "1") (pinfunction "1_1") (pintype "passive"))
      (node (ref "C18") (pin "1") (pinfunction "1_1") (pintype "passive"))
      (node (ref "C24") (pin "1") (pinfunction "1_1") (pintype "passive"))
      (node (ref "C25") (pin "1") (pinfunction "1_1") (pintype "passive"))
      (node (ref "C26") (pin "1") (pinfunction "1_1") (pintype "passive"))
      (node (ref "C27") (pin "1") (pinfunction "1_1") (pintype "passive"))
      (node (ref "C28") (pin "1") (pinfunction "1_1") (pintype "passive"))
      (node (ref "C4") (pin "1") (pinfunction "1_1") (pintype "passive"))
      (node (ref "C5") (pin "1") (pinfunction "1_1") (pintype "passive"))
      (node (ref "C6") (pin "1") (pinfunction "1_1") (pintype "passive"))
      (node (ref "C7") (pin "1") (pinfunction "1_1") (pintype "passive"))
      (node (ref "C8") (pin "1") (pinfunction "1_1") (pintype "passive"))
      (node (ref "C9") (pin "1") (pinfunction "1_1") (pintype "passive"))
      (node (ref "CON1") (pin "2") (pinfunction "VDD_2") (pintype "bidirectional"))
      (node (ref "CON4") (pin "4") (pinfunction "VDD_4") (pintype "bidirectional"))
      (node (ref "IC2") (pin "5") (pinfunction "OUT_5") (pintype "bidirectional"))
      (node (ref "IC6") (pin "4") (pinfunction "VCC_4") (pintype "power_in"))
      (node (ref "J1") (pin "2") (pinfunction "3V3_2") (pintype "power_in"))
      (node (ref "LED1") (pin "1") (pinfunction "1_1") (pintype "bidirectional"))
      (node (ref "LED2") (pin "1") (pinfunction "1_1") (pintype "bidirectional"))
      (node (ref "R1") (pin "1") (pinfunction "1_1") (pintype "passive"))
      (node (ref "R17") (pin "2") (pinfunction "2_2") (pintype "passive"))
      (node (ref "R18") (pin "2") (pinfunction "2_2") (pintype "passive"))
      (node (ref "R19") (pin "2") (pinfunction "2_2") (pintype "passive"))
      (node (ref "R20") (pin "2") (pinfunction "2_2") (pintype "passive"))
      (node (ref "R28") (pin "2") (pinfunction "2_2") (pintype "passive"))
      (node (ref "R40") (pin "2") (pinfunction "2_2") (pintype "passive"))
      (node (ref "R41") (pin "2") (pinfunction "2_2") (pintype "passive"))
      (node (ref "TP4") (pin "TP") (pinfunction "TP_TP") (pintype "input"))
      (node (ref "U1") (pin "10") (pinfunction "VDD_2_10") (pintype "power_in"))
      (node (ref "U1") (pin "19") (pinfunction "AVDD_19") (pintype "power_in"))
      (node (ref "U1") (pin "26") (pinfunction "VDD_3_26") (pintype "power_in"))
      (node (ref "U1") (pin "35") (pinfunction "VUSB_35") (pintype "power_in"))
      (node (ref "U1") (pin "38") (pinfunction "VDD_4_38") (pintype "power_in"))
      (node (ref "U1") (pin "57") (pinfunction "VDD_57") (pintype "power_in"))
      (node (ref "U2") (pin "AVDD") (pinfunction "AVDD_AVDD") (pintype "power_in"))
      (node (ref "U2") (pin "AVDD@2") (pinfunction "AVDD_AVDD@2") (pintype "power_in"))
      (node (ref "U2") (pin "DVDD") (pinfunction "DVDD_DVDD") (pintype "power_in"))
      (node (ref "U2") (pin "VDD_USB") (pinfunction "VDD_USB_VDD_USB") (pintype "power_in"))
    )
    (net (code "2") (name "+3V9") (class "Default")
      (node (ref "C29") (pin "1") (pinfunction "1_1") (pintype "passive"))
      (node (ref "C30") (pin "1") (pinfunction "1_1") (pintype "passive"))
      (node (ref "C31") (pin "1") (pinfunction "1_1") (pintype "passive"))
      (node (ref "FB1") (pin "1") (pinfunction "P$1_1") (pintype "bidirectional"))
      (node (ref "Q1") (pin "2") (pinfunction "E_2") (pintype "passive"))
      (node (ref "R33") (pin "2") (pinfunction "2_2") (pintype "passive"))
      (node (ref "TP3") (pin "TP") (pinfunction "TP_TP") (pintype "input"))
      (node (ref "U3") (pin "P$38") (pinfunction "VBAT_BB_P$38") (pintype "bidirectional"))
      (node (ref "U3") (pin "P$39") (pinfunction "VBAT_BB_P$39") (pintype "bidirectional"))
      (node (ref "U3") (pin "P$62") (pinfunction "VBAT_RF_P$62") (pintype "bidirectional"))
      (node (ref "U3") (pin "P$63") (pinfunction "VBAT_RF_P$63") (pintype "bidirectional"))
    )
    (net (code "3") (name "+5V") (class "Default")
      (node (ref "C1") (pin "1") (pinfunction "1_1") (pintype "passive"))
      (node (ref "C16") (pin "1") (pinfunction "1_1") (pintype "passive"))
      (node (ref "C17") (pin "1") (pinfunction "1_1") (pintype "passive"))
      (node (ref "C21") (pin "1") (pinfunction "1_1") (pintype "passive"))
      (node (ref "FB3") (pin "1") (pinfunction "P$1_1") (pintype "bidirectional"))
      (node (ref "IC1") (pin "1") (pinfunction "EN_1") (pintype "bidirectional"))
      (node (ref "IC1") (pin "2") (pinfunction "IN_2") (pintype "bidirectional"))
      (node (ref "IC2") (pin "1") (pinfunction "IN_1") (pintype "bidirectional"))
      (node (ref "IC2") (pin "3") (pinfunction "EN_3") (pintype "bidirectional"))
      (node (ref "R11") (pin "1") (pinfunction "1_1") (pintype "passive"))
      (node (ref "TP2") (pin "TP") (pinfunction "TP_TP") (pintype "input"))
      (node (ref "U1") (pin "33") (pinfunction "USBID/RF3_33") (pintype "bidirectional"))
      (node (ref "U1") (pin "34") (pinfunction "VBUS_34") (pintype "input"))
    )
    (net (code "4") (name "3G_CTS") (class "Default")
      (node (ref "R37") (pin "1") (pinfunction "1_1") (pintype "passive"))
      (node (ref "U1") (pin "8") (pinfunction "*SS2A/U2BRX/U2ACTS/PMA2/CN11/RG9_8") (pintype "bidirectional"))
    )
    (net (code "5") (name "3G_DTR") (class "Default")
      (node (ref "U1") (pin "3") (pinfunction "ETXD1/PMD7/RE7_3") (pintype "bidirectional"))
      (node (ref "U3") (pin "P$72") (pinfunction "UART_DTR_P$72") (pintype "bidirectional"))
    )
    (net (code "6") (name "3G_POWER_ON") (class "Default")
      (node (ref "R29") (pin "1") (pinfunction "1_1") (pintype "passive"))
      (node (ref "U1") (pin "45") (pinfunction "ECRS/AERXCLK/IC4/PMCS1/PMA14/INT4/RD11_45") (pintype "bidirectional"))
    )
    (net (code "7") (name "3G_REG_ON") (class "Default")
      (node (ref "U1") (pin "43") (pinfunction "AERXD0/ETXD2/*SS1A/U1BRX/*U1ACTS/SDA1/IC2/INT2/RD9_43") (pintype "bidirectional"))
    )
    (net (code "8") (name "3G_RTS") (class "Default")
      (node (ref "R36") (pin "1") (pinfunction "1_1") (pintype "passive"))
      (node (ref "U1") (pin "4") (pinfunction "SCK2A/U2BTX/*U2ARTS/PMA5/CN8/RG6_4") (pintype "bidirectional"))
    )
    (net (code "9") (name "3G_RX") (class "Default")
      (node (ref "R34") (pin "1") (pinfunction "1_1") (pintype "passive"))
      (node (ref "U1") (pin "5") (pinfunction "SDA2A/SDI2A/U2ARX/PMA4/CN9/RG7_5") (pintype "bidirectional"))
    )
    (net (code "10") (name "3G_TX") (class "Default")
      (node (ref "R35") (pin "1") (pinfunction "1_1") (pintype "passive"))
      (node (ref "U1") (pin "6") (pinfunction "SCL2A/SDO2A/U2ATX/PMA3/CN10/RG8_6") (pintype "bidirectional"))
    )
    (net (code "11") (name "BT_RESET") (class "Default")
      (node (ref "J1") (pin "7") (pinfunction "RES_7") (pintype "output"))
      (node (ref "R28") (pin "1") (pinfunction "1_1") (pintype "passive"))
      (node (ref "U1") (pin "22") (pinfunction "AN9/C2OUT/PMA7/RB9_22") (pintype "bidirectional"))
      (node (ref "U2") (pin "RESET") (pinfunction "RESET_RESET") (pintype "input"))
    )
    (net (code "12") (name "BT_RX") (class "Default")
      (node (ref "U1") (pin "21") (pinfunction "AN8/*SS3A/U3BRX/*U3ACTS/C1OUT/RB8_21") (pintype "bidirectional"))
      (node (ref "U2") (pin "P1_6") (pinfunction "P1_6_P1_6") (pintype "bidirectional"))
    )
    (net (code "13") (name "BT_TX") (class "Default")
      (node (ref "U1") (pin "29") (pinfunction "AN14/SCK3A/U3BTX/*U3ARTS/PMALH/PMA1/RB14_29") (pintype "bidirectional"))
      (node (ref "U2") (pin "P1_7") (pinfunction "P1_7_P1_7") (pintype "bidirectional"))
    )
    (net (code "14") (name "BUTTON") (class "Default")
      (node (ref "BT1") (pin "1") (pinfunction "P$1_1") (pintype "bidirectional"))
      (node (ref "BT1") (pin "2") (pinfunction "P$1_2") (pintype "bidirectional"))
      (node (ref "R21") (pin "2") (pinfunction "2_2") (pintype "passive"))
      (node (ref "U1") (pin "14") (pinfunction "AN2/C2IN-/CN4/RB2_14") (pintype "bidirectional"))
    )
    (net (code "15") (name "CC_DC") (class "Default")
      (node (ref "J1") (pin "3") (pinfunction "DC_3") (pintype "output"))
      (node (ref "U2") (pin "P2_2") (pinfunction "P2_2_P2_2") (pintype "bidirectional"))
    )
    (net (code "16") (name "CC_DD") (class "Default")
      (node (ref "J1") (pin "4") (pinfunction "DD_4") (pintype "bidirectional"))
      (node (ref "U2") (pin "P2_1") (pinfunction "P2_1_P2_1") (pintype "bidirectional"))
    )
    (net (code "17") (name "D+") (class "Default")
      (node (ref "R8") (pin "1") (pinfunction "1_1") (pintype "passive"))
      (node (ref "U1") (pin "37") (pinfunction "D+/RG2_37") (pintype "bidirectional"))
    )
    (net (code "18") (name "D-") (class "Default")
      (node (ref "R7") (pin "1") (pinfunction "1_1") (pintype "passive"))
      (node (ref "U1") (pin "36") (pinfunction "D-/RG3_36") (pintype "bidirectional"))
    )
    (net (code "19") (name "GND") (class "Default")
      (node (ref "C1") (pin "2") (pinfunction "2_2") (pintype "passive"))
      (node (ref "C10") (pin "2") (pinfunction "2_2") (pintype "passive"))
      (node (ref "C11") (pin "2") (pinfunction "2_2") (pintype "passive"))
      (node (ref "C12") (pin "2") (pinfunction "2_2") (pintype "passive"))
      (node (ref "C13") (pin "2") (pinfunction "2_2") (pintype "passive"))
      (node (ref "C14") (pin "2") (pinfunction "2_2") (pintype "passive"))
      (node (ref "C15") (pin "2") (pinfunction "2_2") (pintype "passive"))
      (node (ref "C16") (pin "2") (pinfunction "2_2") (pintype "passive"))
      (node (ref "C17") (pin "2") (pinfunction "2_2") (pintype "passive"))
      (node (ref "C18") (pin "2") (pinfunction "2_2") (pintype "passive"))
      (node (ref "C19") (pin "2") (pinfunction "2_2") (pintype "passive"))
      (node (ref "C2") (pin "2") (pinfunction "2_2") (pintype "passive"))
      (node (ref "C20") (pin "2") (pinfunction "2_2") (pintype "passive"))
      (node (ref "C21") (pin "2") (pinfunction "2_2") (pintype "passive"))
      (node (ref "C22") (pin "2") (pinfunction "2_2") (pintype "passive"))
      (node (ref "C23") (pin "2") (pinfunction "2_2") (pintype "passive"))
      (node (ref "C24") (pin "2") (pinfunction "2_2") (pintype "passive"))
      (node (ref "C25") (pin "2") (pinfunction "2_2") (pintype "passive"))
      (node (ref "C26") (pin "2") (pinfunction "2_2") (pintype "passive"))
      (node (ref "C27") (pin "2") (pinfunction "2_2") (pintype "passive"))
      (node (ref "C28") (pin "2") (pinfunction "2_2") (pintype "passive"))
      (node (ref "C29") (pin "2") (pinfunction "2_2") (pintype "passive"))
      (node (ref "C3") (pin "2") (pinfunction "2_2") (pintype "passive"))
      (node (ref "C30") (pin "2") (pinfunction "2_2") (pintype "passive"))
      (node (ref "C31") (pin "2") (pinfunction "2_2") (pintype "passive"))
      (node (ref "C4") (pin "2") (pinfunction "2_2") (pintype "passive"))
      (node (ref "C5") (pin "2") (pinfunction "2_2") (pintype "passive"))
      (node (ref "C6") (pin "2") (pinfunction "2_2") (pintype "passive"))
      (node (ref "C7") (pin "2") (pinfunction "2_2") (pintype "passive"))
      (node (ref "C8") (pin "2") (pinfunction "2_2") (pintype "passive"))
      (node (ref "C9") (pin "2") (pinfunction "2_2") (pintype "passive"))
      (node (ref "CON1") (pin "3") (pinfunction "GND_3") (pintype "bidirectional"))
      (node (ref "CON3") (pin "C5") (pinfunction "GND_C5") (pintype "bidirectional"))
      (node (ref "CON3") (pin "GND1") (pinfunction "GND_GND1") (pintype "bidirectional"))
      (node (ref "CON3") (pin "GND2") (pinfunction "GND_GND2") (pintype "bidirectional"))
      (node (ref "CON3") (pin "GND3") (pinfunction "GND_GND3") (pintype "bidirectional"))
      (node (ref "CON3") (pin "GND4") (pinfunction "GND_GND4") (pintype "bidirectional"))
      (node (ref "CON3") (pin "GND5") (pinfunction "GND_GND5") (pintype "bidirectional"))
      (node (ref "CON3") (pin "GND6") (pinfunction "GND_GND6") (pintype "bidirectional"))
      (node (ref "CON4") (pin "6") (pinfunction "VSS_6") (pintype "bidirectional"))
      (node (ref "CON4") (pin "DET") (pinfunction "DET_DET") (pintype "bidirectional"))
      (node (ref "CON5") (pin "2") (pinfunction "GND_2") (pintype "bidirectional"))
      (node (ref "CON5") (pin "3") (pinfunction "GND_3") (pintype "bidirectional"))
      (node (ref "FB4") (pin "2") (pinfunction "P$2_2") (pintype "bidirectional"))
      (node (ref "FB5") (pin "2") (pinfunction "P$2_2") (pintype "bidirectional"))
      (node (ref "IC1") (pin "3") (pinfunction "GND_3") (pintype "bidirectional"))
      (node (ref "IC1") (pin "6") (pinfunction "B_PAD_6") (pintype "bidirectional"))
      (node (ref "IC2") (pin "2") (pinfunction "GND_2") (pintype "bidirectional"))
      (node (ref "IC3") (pin "2") (pinfunction "GND_2") (pintype "bidirectional"))
      (node (ref "IC3") (pin "4") (pinfunction "~{EN}_4") (pintype "bidirectional"))
      (node (ref "IC4") (pin "2") (pinfunction "GND_2") (pintype "bidirectional"))
      (node (ref "IC4") (pin "5") (pinfunction "GND_5") (pintype "bidirectional"))
      (node (ref "IC5") (pin "2") (pinfunction "AN_2") (pintype "bidirectional"))
      (node (ref "IC6") (pin "2") (pinfunction "GND_2") (pintype "power_in"))
      (node (ref "J1") (pin "1") (pinfunction "GND_1") (pintype "power_in"))
      (node (ref "Q2") (pin "2") (pinfunction "E_2") (pintype "passive"))
      (node (ref "Q3") (pin "2") (pinfunction "E_2") (pintype "passive"))
      (node (ref "R10") (pin "2") (pinfunction "2_2") (pintype "passive"))
      (node (ref "R12") (pin "2") (pinfunction "2_2") (pintype "passive"))
      (node (ref "R13") (pin "2") (pinfunction "2_2") (pintype "passive"))
      (node (ref "R21") (pin "1") (pinfunction "1_1") (pintype "passive"))
      (node (ref "R30") (pin "2") (pinfunction "2_2") (pintype "passive"))
      (node (ref "R32") (pin "2") (pinfunction "2_2") (pintype "passive"))
      (node (ref "R39") (pin "2") (pinfunction "2_2") (pintype "passive"))
      (node (ref "R5") (pin "2") (pinfunction "2_2") (pintype "passive"))
      (node (ref "R9") (pin "1") (pinfunction "1_1") (pintype "passive"))
      (node (ref "TP5") (pin "TP") (pinfunction "TP_TP") (pintype "input"))
      (node (ref "TP6") (pin "TP") (pinfunction "TP_TP") (pintype "input"))
      (node (ref "TP7") (pin "TP") (pinfunction "TP_TP") (pintype "input"))
      (node (ref "U1") (pin "20") (pinfunction "AVSS_20") (pintype "power_in"))
      (node (ref "U1") (pin "25") (pinfunction "VSS_3_25") (pintype "power_in"))
      (node (ref "U1") (pin "41") (pinfunction "VSS_41") (pintype "power_in"))
      (node (ref "U1") (pin "9") (pinfunction "VSS_2_9") (pintype "power_in"))
      (node (ref "U2") (pin "GND") (pinfunction "GND_GND") (pintype "power_in"))
      (node (ref "U2") (pin "GND@2") (pinfunction "GND_GND@2") (pintype "power_in"))
      (node (ref "U2") (pin "GND@3") (pinfunction "GND_GND@3") (pintype "power_in"))
      (node (ref "U2") (pin "GND@4") (pinfunction "GND_GND@4") (pintype "power_in"))
      (node (ref "U3") (pin "P$1") (pinfunction "GND_P$1") (pintype "bidirectional"))
      (node (ref "U3") (pin "P$10") (pinfunction "GND_P$10") (pintype "bidirectional"))
      (node (ref "U3") (pin "P$14") (pinfunction "GND_P$14") (pintype "bidirectional"))
      (node (ref "U3") (pin "P$2") (pinfunction "GND_P$2") (pintype "bidirectional"))
      (node (ref "U3") (pin "P$37") (pinfunction "GND_P$37") (pintype "bidirectional"))
      (node (ref "U3") (pin "P$40") (pinfunction "GND_P$40") (pintype "bidirectional"))
      (node (ref "U3") (pin "P$41") (pinfunction "GND_P$41") (pintype "bidirectional"))
      (node (ref "U3") (pin "P$43") (pinfunction "GND_P$43") (pintype "bidirectional"))
      (node (ref "U3") (pin "P$5") (pinfunction "GND_P$5") (pintype "bidirectional"))
      (node (ref "U3") (pin "P$57") (pinfunction "GND_P$57") (pintype "bidirectional"))
      (node (ref "U3") (pin "P$58") (pinfunction "GND_P$58") (pintype "bidirectional"))
      (node (ref "U3") (pin "P$60") (pinfunction "GND_P$60") (pintype "bidirectional"))
      (node (ref "U3") (pin "P$61") (pinfunction "GND_P$61") (pintype "bidirectional"))
      (node (ref "U3") (pin "P$64") (pinfunction "GND_P$64") (pintype "bidirectional"))
      (node (ref "U3") (pin "P$65") (pinfunction "GND_P$65") (pintype "bidirectional"))
      (node (ref "U3") (pin "P$77") (pinfunction "GND_P$77") (pintype "bidirectional"))
      (node (ref "U3") (pin "P$78") (pinfunction "GND_P$78") (pintype "bidirectional"))
      (node (ref "U3") (pin "P$80") (pinfunction "GND_P$80") (pintype "bidirectional"))
    )
    (net (code "20") (name "GPS_ANT") (class "Default")
      (node (ref "R38") (pin "2") (pinfunction "2_2") (pintype "passive"))
      (node (ref "U3") (pin "P$79") (pinfunction "GPS_ANT_P$79") (pintype "bidirectional"))
    )
    (net (code "21") (name "LED1_B") (class "Default")
      (node (ref "R22") (pin "1") (pinfunction "1_1") (pintype "passive"))
      (node (ref "U1") (pin "59") (pinfunction "AETXD0/ERXD2/RF1_59") (pintype "bidirectional"))
    )
    (net (code "22") (name "LED1_G") (class "Default")
      (node (ref "R23") (pin "1") (pinfunction "1_1") (pintype "passive"))
      (node (ref "U1") (pin "61") (pinfunction "ERXD0/PMD1/RE1_61") (pintype "bidirectional"))
    )
    (net (code "23") (name "LED1_R") (class "Default")
      (node (ref "R24") (pin "1") (pinfunction "1_1") (pintype "passive"))
      (node (ref "U1") (pin "60") (pinfunction "ERXD1/PMD0/RE0_60") (pintype "bidirectional"))
    )
    (net (code "24") (name "LED2_B") (class "Default")
      (node (ref "R25") (pin "1") (pinfunction "1_1") (pintype "passive"))
      (node (ref "U1") (pin "62") (pinfunction "ERXDV/PMD2/RE2_62") (pintype "bidirectional"))
    )
    (net (code "25") (name "LED2_G") (class "Default")
      (node (ref "R26") (pin "1") (pinfunction "1_1") (pintype "passive"))
      (node (ref "U1") (pin "64") (pinfunction "ERXERR/PMD4/RE4_64") (pintype "bidirectional"))
    )
    (net (code "26") (name "LED2_R") (class "Default")
      (node (ref "R27") (pin "1") (pinfunction "1_1") (pintype "passive"))
      (node (ref "U1") (pin "63") (pinfunction "ERXCLK/PMD3/RE3_63") (pintype "bidirectional"))
    )
    (net (code "27") (name "MAIN_ANT") (class "Default")
      (node (ref "CON5") (pin "1") (pinfunction "FEED_1") (pintype "bidirectional"))
      (node (ref "U3") (pin "P$59") (pinfunction "MAIN_ANT_P$59") (pintype "bidirectional"))
    )
    (net (code "28") (name "MCLR") (class "Default")
      (node (ref "CON1") (pin "1") (pinfunction "MCLR_1") (pintype "bidirectional"))
      (node (ref "R2") (pin "1") (pinfunction "1_1") (pintype "passive"))
      (node (ref "U1") (pin "7") (pinfunction "*MCLR_7") (pintype "input"))
    )
    (net (code "29") (name "MEM_SCL") (class "Default")
      (node (ref "IC6") (pin "1") (pinfunction "SCL_1") (pintype "input"))
      (node (ref "R40") (pin "1") (pinfunction "1_1") (pintype "passive"))
      (node (ref "U1") (pin "32") (pinfunction "SCL3A/SDO3A/U3ATX/PMA8/CN18/RF5_32") (pintype "bidirectional"))
    )
    (net (code "30") (name "MEM_SDA") (class "Default")
      (node (ref "IC6") (pin "3") (pinfunction "SDA_3") (pintype "bidirectional"))
      (node (ref "R41") (pin "1") (pinfunction "1_1") (pintype "passive"))
      (node (ref "U1") (pin "31") (pinfunction "SDA3A/SDI3A/U3ARX/PMA9/CN17/RF4_31") (pintype "bidirectional"))
    )
    (net (code "31") (name "NET_STATUS") (class "Default")
      (node (ref "R31") (pin "1") (pinfunction "1_1") (pintype "passive"))
      (node (ref "U1") (pin "48") (pinfunction "SOSCO/T1CK/CN0/RC14_48") (pintype "bidirectional"))
      (node (ref "U3") (pin "P$51") (pinfunction "GPIO1_P$51") (pintype "bidirectional"))
    )
    (net (code "32") (name "Net-(ANT1-PadFEED)") (class "Default")
      (node (ref "ANT1") (pin "FEED") (pinfunction "FEED_FEED") (pintype "bidirectional"))
      (node (ref "R38") (pin "1") (pinfunction "1_1") (pintype "passive"))
      (node (ref "R39") (pin "1") (pinfunction "1_1") (pintype "passive"))
    )
    (net (code "33") (name "Net-(C2-Pad1)") (class "Default")
      (node (ref "C2") (pin "1") (pinfunction "1_1") (pintype "passive"))
      (node (ref "R1") (pin "2") (pinfunction "2_2") (pintype "passive"))
      (node (ref "R2") (pin "2") (pinfunction "2_2") (pintype "passive"))
    )
    (net (code "34") (name "Net-(CON2-D+)") (class "Default")
      (node (ref "CON2") (pin "3") (pinfunction "D+_3") (pintype "bidirectional"))
      (node (ref "IC4") (pin "6") (pinfunction "A_6") (pintype "bidirectional"))
      (node (ref "R10") (pin "1") (pinfunction "1_1") (pintype "passive"))
      (node (ref "R8") (pin "2") (pinfunction "2_2") (pintype "passive"))
    )
    (net (code "35") (name "Net-(CON2-D-)") (class "Default")
      (node (ref "CON2") (pin "2") (pinfunction "D-_2") (pintype "bidirectional"))
      (node (ref "IC4") (pin "4") (pinfunction "B_4") (pintype "bidirectional"))
      (node (ref "R7") (pin "2") (pinfunction "2_2") (pintype "passive"))
      (node (ref "R9") (pin "2") (pinfunction "2_2") (pintype "passive"))
    )
    (net (code "36") (name "Net-(CON2-GND)") (class "Default")
      (node (ref "CON2") (pin "5") (pinfunction "GND_5") (pintype "bidirectional"))
      (node (ref "FB4") (pin "1") (pinfunction "P$1_1") (pintype "bidirectional"))
    )
    (net (code "37") (name "Net-(CON2-VBUS)") (class "Default")
      (node (ref "CON2") (pin "1") (pinfunction "VBUS_1") (pintype "bidirectional"))
      (node (ref "FB2") (pin "2") (pinfunction "P$2_2") (pintype "bidirectional"))
    )
    (net (code "38") (name "Net-(CON3-CLK)") (class "Default")
      (node (ref "CON3") (pin "C3") (pinfunction "CLK_C3") (pintype "bidirectional"))
      (node (ref "IC5") (pin "6") (pinfunction "C5_6") (pintype "bidirectional"))
      (node (ref "R14") (pin "1") (pinfunction "1_1") (pintype "passive"))
    )
    (net (code "39") (name "Net-(CON3-I{slash}O)") (class "Default")
      (node (ref "CON3") (pin "C7") (pinfunction "I/O_C7") (pintype "bidirectional"))
      (node (ref "IC5") (pin "5") (pinfunction "C4_5") (pintype "bidirectional"))
      (node (ref "R15") (pin "1") (pinfunction "1_1") (pintype "passive"))
    )
    (net (code "40") (name "Net-(CON3-RST)") (class "Default")
      (node (ref "CON3") (pin "C2") (pinfunction "RST_C2") (pintype "bidirectional"))
      (node (ref "IC5") (pin "4") (pinfunction "C3_4") (pintype "bidirectional"))
      (node (ref "R16") (pin "1") (pinfunction "1_1") (pintype "passive"))
    )
    (net (code "41") (name "Net-(FB1-P$2)") (class "Default")
      (node (ref "C19") (pin "1") (pinfunction "1_1") (pintype "passive"))
      (node (ref "FB1") (pin "2") (pinfunction "P$2_2") (pintype "bidirectional"))
      (node (ref "IC1") (pin "4") (pinfunction "OUT_4") (pintype "bidirectional"))
      (node (ref "R4") (pin "1") (pinfunction "1_1") (pintype "passive"))
    )
    (net (code "42") (name "Net-(FB3-P$2)") (class "Default")
      (node (ref "FB3") (pin "2") (pinfunction "P$2_2") (pintype "bidirectional"))
      (node (ref "IC3") (pin "1") (pinfunction "OUT_1") (pintype "bidirectional"))
      (node (ref "R6") (pin "2") (pinfunction "2_2") (pintype "passive"))
    )
    (net (code "43") (name "Net-(FB5-P$1)") (class "Default")
      (node (ref "CON2") (pin "S1") (pinfunction "SH_S1") (pintype "bidirectional"))
      (node (ref "CON2") (pin "S2") (pinfunction "SH_S2") (pintype "bidirectional"))
      (node (ref "CON2") (pin "S3") (pinfunction "SH_S3") (pintype "bidirectional"))
      (node (ref "CON2") (pin "S4") (pinfunction "SH_S4") (pintype "bidirectional"))
      (node (ref "CON2") (pin "S5") (pinfunction "SH_S5") (pintype "bidirectional"))
      (node (ref "CON2") (pin "S6") (pinfunction "SH_S6") (pintype "bidirectional"))
      (node (ref "FB5") (pin "1") (pinfunction "P$1_1") (pintype "bidirectional"))
    )
    (net (code "44") (name "Net-(IC1-ADJ)") (class "Default")
      (node (ref "IC1") (pin "5") (pinfunction "ADJ_5") (pintype "bidirectional"))
      (node (ref "R4") (pin "2") (pinfunction "2_2") (pintype "passive"))
      (node (ref "R5") (pin "1") (pinfunction "1_1") (pintype "passive"))
    )
    (net (code "45") (name "Net-(LED1-Pad2)") (class "Default")
      (node (ref "LED1") (pin "2") (pinfunction "2_2") (pintype "bidirectional"))
      (node (ref "R24") (pin "2") (pinfunction "2_2") (pintype "passive"))
    )
    (net (code "46") (name "Net-(LED1-Pad3)") (class "Default")
      (node (ref "LED1") (pin "3") (pinfunction "3_3") (pintype "bidirectional"))
      (node (ref "R23") (pin "2") (pinfunction "2_2") (pintype "passive"))
    )
    (net (code "47") (name "Net-(LED1-Pad4)") (class "Default")
      (node (ref "LED1") (pin "4") (pinfunction "4_4") (pintype "bidirectional"))
      (node (ref "R22") (pin "2") (pinfunction "2_2") (pintype "passive"))
    )
    (net (code "48") (name "Net-(LED2-Pad2)") (class "Default")
      (node (ref "LED2") (pin "2") (pinfunction "2_2") (pintype "bidirectional"))
      (node (ref "R27") (pin "2") (pinfunction "2_2") (pintype "passive"))
    )
    (net (code "49") (name "Net-(LED2-Pad3)") (class "Default")
      (node (ref "LED2") (pin "3") (pinfunction "3_3") (pintype "bidirectional"))
      (node (ref "R26") (pin "2") (pinfunction "2_2") (pintype "passive"))
    )
    (net (code "50") (name "Net-(LED2-Pad4)") (class "Default")
      (node (ref "LED2") (pin "4") (pinfunction "4_4") (pintype "bidirectional"))
      (node (ref "R25") (pin "2") (pinfunction "2_2") (pintype "passive"))
    )
    (net (code "51") (name "Net-(LED3-PadA)") (class "Default")
      (node (ref "LED3") (pin "A") (pinfunction "A_A") (pintype "passive"))
      (node (ref "R33") (pin "1") (pinfunction "1_1") (pintype "passive"))
    )
    (net (code "52") (name "Net-(Q1-B)") (class "Default")
      (node (ref "Q1") (pin "1") (pinfunction "B_1") (pintype "passive"))
      (node (ref "R11") (pin "2") (pinfunction "2_2") (pintype "passive"))
      (node (ref "R12") (pin "1") (pinfunction "1_1") (pintype "passive"))
    )
    (net (code "53") (name "Net-(Q1-C)") (class "Default")
      (node (ref "Q1") (pin "3") (pinfunction "C_3") (pintype "passive"))
      (node (ref "R13") (pin "1") (pinfunction "1_1") (pintype "passive"))
    )
    (net (code "54") (name "Net-(Q2-B)") (class "Default")
      (node (ref "Q2") (pin "1") (pinfunction "B_1") (pintype "passive"))
      (node (ref "R29") (pin "2") (pinfunction "2_2") (pintype "passive"))
      (node (ref "R30") (pin "1") (pinfunction "1_1") (pintype "passive"))
    )
    (net (code "55") (name "Net-(Q3-B)") (class "Default")
      (node (ref "Q3") (pin "1") (pinfunction "B_1") (pintype "passive"))
      (node (ref "R31") (pin "2") (pinfunction "2_2") (pintype "passive"))
      (node (ref "R32") (pin "1") (pinfunction "1_1") (pintype "passive"))
    )
    (net (code "56") (name "Net-(Q3-C)") (class "Default")
      (node (ref "LED3") (pin "C") (pinfunction "C_C") (pintype "passive"))
      (node (ref "Q3") (pin "3") (pinfunction "C_3") (pintype "passive"))
    )
    (net (code "57") (name "Net-(U3-UART_CTS)") (class "Default")
      (node (ref "R36") (pin "2") (pinfunction "2_2") (pintype "passive"))
      (node (ref "U3") (pin "P$67") (pinfunction "UART_CTS_P$67") (pintype "bidirectional"))
    )
    (net (code "58") (name "Net-(U3-UART_RTS)") (class "Default")
      (node (ref "R37") (pin "2") (pinfunction "2_2") (pintype "passive"))
      (node (ref "U3") (pin "P$66") (pinfunction "UART_RTS_P$66") (pintype "bidirectional"))
    )
    (net (code "59") (name "Net-(U3-UART_RXD)") (class "Default")
      (node (ref "R35") (pin "2") (pinfunction "2_2") (pintype "passive"))
      (node (ref "U3") (pin "P$68") (pinfunction "UART_RXD_P$68") (pintype "bidirectional"))
    )
    (net (code "60") (name "Net-(U3-UART_TXD)") (class "Default")
      (node (ref "R34") (pin "2") (pinfunction "2_2") (pintype "passive"))
      (node (ref "U3") (pin "P$71") (pinfunction "UART_TXD_P$71") (pintype "bidirectional"))
    )
    (net (code "61") (name "OSC1") (class "Default")
      (node (ref "C14") (pin "1") (pinfunction "1_1") (pintype "passive"))
      (node (ref "R3") (pin "1") (pinfunction "1_1") (pintype "passive"))
      (node (ref "U1") (pin "39") (pinfunction "OSC1/CLKI/RC12_39") (pintype "bidirectional"))
      (node (ref "Y1") (pin "P$2") (pinfunction "2_P$2") (pintype "passive"))
    )
    (net (code "62") (name "OSC2") (class "Default")
      (node (ref "C15") (pin "1") (pinfunction "1_1") (pintype "passive"))
      (node (ref "R3") (pin "2") (pinfunction "2_2") (pintype "passive"))
      (node (ref "U1") (pin "40") (pinfunction "OSC2/CLKO/RC15_40") (pintype "bidirectional"))
      (node (ref "Y1") (pin "P$1") (pinfunction "1_P$1") (pintype "passive"))
    )
    (net (code "63") (name "PGEC1") (class "Default")
      (node (ref "CON1") (pin "5") (pinfunction "PGC_5") (pintype "bidirectional"))
      (node (ref "U1") (pin "15") (pinfunction "PGEC1/AN1/VREF-/CVREF-/CN3/RB1_15") (pintype "bidirectional"))
    )
    (net (code "64") (name "PGED1") (class "Default")
      (node (ref "CON1") (pin "4") (pinfunction "PGD_4") (pintype "bidirectional"))
      (node (ref "U1") (pin "16") (pinfunction "PGED1/AN0/VREF+/CVREF+/PMA6/CN2/RB0_16") (pintype "bidirectional"))
    )
    (net (code "65") (name "POWER_ON") (class "Default")
      (node (ref "Q2") (pin "3") (pinfunction "C_3") (pintype "passive"))
      (node (ref "U3") (pin "P$3") (pinfunction "POWER_ON_P$3") (pintype "bidirectional"))
    )
    (net (code "66") (name "RB6") (class "Default")
      (node (ref "U1") (pin "17") (pinfunction "PGEC2/AN6/OCFA/RB6_17") (pintype "bidirectional"))
    )
    (net (code "67") (name "RB7") (class "Default")
      (node (ref "U1") (pin "18") (pinfunction "PGED2/AN7/RB7_18") (pintype "bidirectional"))
    )
    (net (code "68") (name "RB10") (class "Default")
      (node (ref "U1") (pin "23") (pinfunction "TMS/AN10/CVREFOUT/PMA13/RB10_23") (pintype "bidirectional"))
    )
    (net (code "69") (name "RB11") (class "Default")
      (node (ref "U1") (pin "24") (pinfunction "TDO/AN11/PMA12/RB11_24") (pintype "bidirectional"))
    )
    (net (code "70") (name "RB12") (class "Default")
      (node (ref "U1") (pin "27") (pinfunction "TCK/AN12/PMA11/RB12_27") (pintype "bidirectional"))
    )
    (net (code "71") (name "RB13") (class "Default")
      (node (ref "U1") (pin "28") (pinfunction "TDI/AN13/PMA10/RB13_28") (pintype "bidirectional"))
    )
    (net (code "72") (name "RD0") (class "Default")
      (node (ref "U1") (pin "46") (pinfunction "OC1/INT0/RD0_46") (pintype "bidirectional"))
    )
    (net (code "73") (name "RD5") (class "Default")
      (node (ref "U1") (pin "53") (pinfunction "PMRD/CN14/RD5_53") (pintype "bidirectional"))
    )
    (net (code "74") (name "RD6") (class "Default")
      (node (ref "U1") (pin "54") (pinfunction "AETXEN/ETXERR/CN15/RD6_54") (pintype "bidirectional"))
    )
    (net (code "75") (name "RD7") (class "Default")
      (node (ref "U1") (pin "55") (pinfunction "ETXCLK/AERXERR/CN16/RD7_55") (pintype "bidirectional"))
    )
    (net (code "76") (name "RD8") (class "Default")
      (node (ref "U1") (pin "42") (pinfunction "RTCC/AERXD1/ETXD3/IC1/INT1/RD8_42") (pintype "bidirectional"))
    )
    (net (code "77") (name "RD10") (class "Default")
      (node (ref "U1") (pin "44") (pinfunction "ECOL/AERXDV/SCL1/IC3/PMCS2/PMA15/INT3/RD10_44") (pintype "bidirectional"))
    )
    (net (code "78") (name "RE5") (class "Default")
      (node (ref "U1") (pin "1") (pinfunction "ETXEN/PMD5/RE5_1") (pintype "bidirectional"))
    )
    (net (code "79") (name "RE6") (class "Default")
      (node (ref "U1") (pin "2") (pinfunction "ETXD0/PMD6/RE6_2") (pintype "bidirectional"))
    )
    (net (code "80") (name "RF0") (class "Default")
      (node (ref "U1") (pin "58") (pinfunction "AETXD1/ERXD3/RF0_58") (pintype "bidirectional"))
    )
    (net (code "81") (name "SCK1") (class "Default")
      (node (ref "CON4") (pin "5") (pinfunction "CLK/SCLK_5") (pintype "bidirectional"))
      (node (ref "U1") (pin "49") (pinfunction "EMDIO/SCK1A/U1BTX/U1ARTS/OC2/RD1_49") (pintype "bidirectional"))
    )
    (net (code "82") (name "SDI1") (class "Default")
      (node (ref "CON4") (pin "7") (pinfunction "DATA0/DO_7") (pintype "bidirectional"))
      (node (ref "R20") (pin "1") (pinfunction "1_1") (pintype "passive"))
      (node (ref "U1") (pin "50") (pinfunction "SDA1A/SDI1A/U1ARX/OC3/RD2_50") (pintype "bidirectional"))
    )
    (net (code "83") (name "SDO1") (class "Default")
      (node (ref "CON4") (pin "3") (pinfunction "CMD/DI_3") (pintype "bidirectional"))
      (node (ref "R19") (pin "1") (pinfunction "1_1") (pintype "passive"))
      (node (ref "U1") (pin "51") (pinfunction "SCL1A/SDO1A/U1ATX/OC4/RD3_51") (pintype "bidirectional"))
    )
    (net (code "84") (name "SD_CS") (class "Default")
      (node (ref "CON4") (pin "2") (pinfunction "CD/DATA3/CS_2") (pintype "bidirectional"))
      (node (ref "R18") (pin "1") (pinfunction "1_1") (pintype "passive"))
      (node (ref "U1") (pin "52") (pinfunction "OC5/IC5/PMWR/CN13/RD4_52") (pintype "bidirectional"))
    )
    (net (code "85") (name "SD_DETECT") (class "Default")
      (node (ref "CON4") (pin "SW") (pinfunction "SW_SW") (pintype "bidirectional"))
      (node (ref "R17") (pin "1") (pinfunction "1_1") (pintype "passive"))
      (node (ref "U1") (pin "47") (pinfunction "SOSCI/CN1/RC13_47") (pintype "bidirectional"))
    )
    (net (code "86") (name "SIM_RESET") (class "Default")
      (node (ref "R16") (pin "2") (pinfunction "2_2") (pintype "passive"))
      (node (ref "U3") (pin "P$18") (pinfunction "USIM_RESET_P$18") (pintype "bidirectional"))
    )
    (net (code "87") (name "USIM_CLK") (class "Default")
      (node (ref "R14") (pin "2") (pinfunction "2_2") (pintype "passive"))
      (node (ref "U3") (pin "P$19") (pinfunction "USIM_CLK_P$19") (pintype "bidirectional"))
    )
    (net (code "88") (name "USIM_DATA") (class "Default")
      (node (ref "R15") (pin "2") (pinfunction "2_2") (pintype "passive"))
      (node (ref "U3") (pin "P$17") (pinfunction "USIM_DATA_P$17") (pintype "bidirectional"))
    )
    (net (code "89") (name "VBUS") (class "Default")
      (node (ref "C20") (pin "1") (pinfunction "1_1") (pintype "passive"))
      (node (ref "FB2") (pin "1") (pinfunction "P$1_1") (pintype "bidirectional"))
      (node (ref "IC3") (pin "5") (pinfunction "IN_5") (pintype "bidirectional"))
      (node (ref "R6") (pin "1") (pinfunction "1_1") (pintype "passive"))
    )
    (net (code "90") (name "VCAP") (class "Default")
      (node (ref "C3") (pin "1") (pinfunction "1_1") (pintype "passive"))
      (node (ref "TP1") (pin "TP") (pinfunction "TP_TP") (pintype "input"))
      (node (ref "U1") (pin "56") (pinfunction "VCAP/VDDCORE_56") (pintype "power_in"))
    )
    (net (code "91") (name "V_USIM") (class "Default")
      (node (ref "C22") (pin "1") (pinfunction "1_1") (pintype "passive"))
      (node (ref "C23") (pin "1") (pinfunction "1_1") (pintype "passive"))
      (node (ref "CON3") (pin "C1") (pinfunction "VCC_C1") (pintype "bidirectional"))
      (node (ref "IC5") (pin "1") (pinfunction "C1_1") (pintype "bidirectional"))
      (node (ref "U3") (pin "P$20") (pinfunction "V_USIM_P$20") (pintype "bidirectional"))
    )
    (net (code "92") (name "ZIG_CS") (class "Default")
      (node (ref "U1") (pin "30") (pinfunction "AN15/EMDC/OCFB/PMALL/PMA0/CN12/RB15_30") (pintype "bidirectional"))
    )
    (net (code "93") (name "ZIG_INT") (class "Default")
      (node (ref "U1") (pin "11") (pinfunction "AN5/C1IN+/VBUSON/CN7/RB5_11") (pintype "bidirectional"))
    )
    (net (code "94") (name "ZIG_RESET") (class "Default")
      (node (ref "U1") (pin "13") (pinfunction "AN3/C2IN+/CN5/RB3_13") (pintype "bidirectional"))
    )
    (net (code "95") (name "ZIG_WAKE") (class "Default")
      (node (ref "U1") (pin "12") (pinfunction "AN4/C1IN-/CN6/RB4_12") (pintype "bidirectional"))
    )
    (net (code "96") (name "unconnected-(CON1-LVP-Pad6)") (class "Default")
      (node (ref "CON1") (pin "6") (pinfunction "LVP_6") (pintype "bidirectional"))
    )
    (net (code "97") (name "unconnected-(CON2-ID-Pad4)") (class "Default")
      (node (ref "CON2") (pin "4") (pinfunction "ID_4") (pintype "bidirectional"))
    )
    (net (code "98") (name "unconnected-(CON3-VPP-PadC6)") (class "Default")
      (node (ref "CON3") (pin "C6") (pinfunction "VPP_C6") (pintype "bidirectional"))
    )
    (net (code "99") (name "unconnected-(CON4-DATA1{slash}X-Pad8)") (class "Default")
      (node (ref "CON4") (pin "8") (pinfunction "DATA1/X_8") (pintype "bidirectional"))
    )
    (net (code "100") (name "unconnected-(CON4-DATA2{slash}X-Pad1)") (class "Default")
      (node (ref "CON4") (pin "1") (pinfunction "DATA2/X_1") (pintype "bidirectional"))
    )
    (net (code "101") (name "unconnected-(IC3-~{FLT}-Pad3)") (class "Default")
      (node (ref "IC3") (pin "3") (pinfunction "~{FLT}_3") (pintype "bidirectional"))
    )
    (net (code "102") (name "unconnected-(IC5-C2-Pad3)") (class "Default")
      (node (ref "IC5") (pin "3") (pinfunction "C2_3") (pintype "bidirectional"))
    )
    (net (code "103") (name "unconnected-(U2-PadP0_0)") (class "Default")
      (node (ref "U2") (pin "P0_0") (pinfunction "P0_0_P0_0") (pintype "bidirectional"))
    )
    (net (code "104") (name "unconnected-(U2-PadP0_1)") (class "Default")
      (node (ref "U2") (pin "P0_1") (pinfunction "P0_1_P0_1") (pintype "bidirectional"))
    )
    (net (code "105") (name "unconnected-(U2-PadP0_2)") (class "Default")
      (node (ref "U2") (pin "P0_2") (pinfunction "P0_2_P0_2") (pintype "bidirectional"))
    )
    (net (code "106") (name "unconnected-(U2-PadP0_3)") (class "Default")
      (node (ref "U2") (pin "P0_3") (pinfunction "P0_3_P0_3") (pintype "bidirectional"))
    )
    (net (code "107") (name "unconnected-(U2-PadP0_4)") (class "Default")
      (node (ref "U2") (pin "P0_4") (pinfunction "P0_4_P0_4") (pintype "bidirectional"))
    )
    (net (code "108") (name "unconnected-(U2-PadP0_5)") (class "Default")
      (node (ref "U2") (pin "P0_5") (pinfunction "P0_5_P0_5") (pintype "bidirectional"))
    )
    (net (code "109") (name "unconnected-(U2-PadP0_6)") (class "Default")
      (node (ref "U2") (pin "P0_6") (pinfunction "P0_6_P0_6") (pintype "bidirectional"))
    )
    (net (code "110") (name "unconnected-(U2-PadP0_7)") (class "Default")
      (node (ref "U2") (pin "P0_7") (pinfunction "P0_7_P0_7") (pintype "bidirectional"))
    )
    (net (code "111") (name "unconnected-(U2-PadP1_0)") (class "Default")
      (node (ref "U2") (pin "P1_0") (pinfunction "P1_0_P1_0") (pintype "bidirectional"))
    )
    (net (code "112") (name "unconnected-(U2-PadP1_1)") (class "Default")
      (node (ref "U2") (pin "P1_1") (pinfunction "P1_1_P1_1") (pintype "bidirectional"))
    )
    (net (code "113") (name "unconnected-(U2-PadP1_2)") (class "Default")
      (node (ref "U2") (pin "P1_2") (pinfunction "P1_2_P1_2") (pintype "bidirectional"))
    )
    (net (code "114") (name "unconnected-(U2-PadP1_3)") (class "Default")
      (node (ref "U2") (pin "P1_3") (pinfunction "P1_3_P1_3") (pintype "bidirectional"))
    )
    (net (code "115") (name "unconnected-(U2-PadP1_4)") (class "Default")
      (node (ref "U2") (pin "P1_4") (pinfunction "P1_4_P1_4") (pintype "bidirectional"))
    )
    (net (code "116") (name "unconnected-(U2-PadP1_5)") (class "Default")
      (node (ref "U2") (pin "P1_5") (pinfunction "P1_5_P1_5") (pintype "bidirectional"))
    )
    (net (code "117") (name "unconnected-(U2-PadP2_0)") (class "Default")
      (node (ref "U2") (pin "P2_0") (pinfunction "P2_0_P2_0") (pintype "bidirectional"))
    )
    (net (code "118") (name "unconnected-(U2-PadUSB+)") (class "Default")
      (node (ref "U2") (pin "USB+") (pinfunction "USB+_USB+") (pintype "bidirectional"))
    )
    (net (code "119") (name "unconnected-(U2-PadUSB-)") (class "Default")
      (node (ref "U2") (pin "USB-") (pinfunction "USB-_USB-") (pintype "bidirectional"))
    )
    (net (code "120") (name "unconnected-(U3-ADC1-PadP$47)") (class "Default")
      (node (ref "U3") (pin "P$47") (pinfunction "ADC1_P$47") (pintype "bidirectional"))
    )
    (net (code "121") (name "unconnected-(U3-ADC2-PadP$46)") (class "Default")
      (node (ref "U3") (pin "P$46") (pinfunction "ADC2_P$46") (pintype "bidirectional"))
    )
    (net (code "122") (name "unconnected-(U3-CURRENT_SINK-PadP$45)") (class "Default")
      (node (ref "U3") (pin "P$45") (pinfunction "CURRENT_SINK_P$45") (pintype "bidirectional"))
    )
    (net (code "123") (name "unconnected-(U3-EAR1N-PadP$25)") (class "Default")
      (node (ref "U3") (pin "P$25") (pinfunction "EAR1N_P$25") (pintype "bidirectional"))
    )
    (net (code "124") (name "unconnected-(U3-EAR1P-PadP$26)") (class "Default")
      (node (ref "U3") (pin "P$26") (pinfunction "EAR1P_P$26") (pintype "bidirectional"))
    )
    (net (code "125") (name "unconnected-(U3-GPIO4-PadP$54)") (class "Default")
      (node (ref "U3") (pin "P$54") (pinfunction "GPIO4_P$54") (pintype "bidirectional"))
    )
    (net (code "126") (name "unconnected-(U3-GPIO40-PadP$49)") (class "Default")
      (node (ref "U3") (pin "P$49") (pinfunction "GPIO40_P$49") (pintype "bidirectional"))
    )
    (net (code "127") (name "unconnected-(U3-GPIO41-PadP$52)") (class "Default")
      (node (ref "U3") (pin "P$52") (pinfunction "GPIO41_P$52") (pintype "bidirectional"))
    )
    (net (code "128") (name "unconnected-(U3-GPIO42-PadP$53)") (class "Default")
      (node (ref "U3") (pin "P$53") (pinfunction "GPIO42_P$53") (pintype "bidirectional"))
    )
    (net (code "129") (name "unconnected-(U3-GPIO43-PadP$50)") (class "Default")
      (node (ref "U3") (pin "P$50") (pinfunction "GPIO43_P$50") (pintype "bidirectional"))
    )
    (net (code "130") (name "unconnected-(U3-GPIO44-PadP$48)") (class "Default")
      (node (ref "U3") (pin "P$48") (pinfunction "GPIO44_P$48") (pintype "bidirectional"))
    )
    (net (code "131") (name "unconnected-(U3-I2C_SCL-PadP$55)") (class "Default")
      (node (ref "U3") (pin "P$55") (pinfunction "I2C_SCL_P$55") (pintype "bidirectional"))
    )
    (net (code "132") (name "unconnected-(U3-I2C_SDA-PadP$56)") (class "Default")
      (node (ref "U3") (pin "P$56") (pinfunction "I2C_SDA_P$56") (pintype "bidirectional"))
    )
    (net (code "133") (name "unconnected-(U3-KEYPAD_0-PadP$29)") (class "Default")
      (node (ref "U3") (pin "P$29") (pinfunction "KEYPAD_0_P$29") (pintype "bidirectional"))
    )
    (net (code "134") (name "unconnected-(U3-KEYPAD_1-PadP$33)") (class "Default")
      (node (ref "U3") (pin "P$33") (pinfunction "KEYPAD_1_P$33") (pintype "bidirectional"))
    )
    (net (code "135") (name "unconnected-(U3-KEYPAD_2-PadP$30)") (class "Default")
      (node (ref "U3") (pin "P$30") (pinfunction "KEYPAD_2_P$30") (pintype "bidirectional"))
    )
    (net (code "136") (name "unconnected-(U3-KEYPAD_3-PadP$35)") (class "Default")
      (node (ref "U3") (pin "P$35") (pinfunction "KEYPAD_3_P$35") (pintype "bidirectional"))
    )
    (net (code "137") (name "unconnected-(U3-KEYPAD_4-PadP$34)") (class "Default")
      (node (ref "U3") (pin "P$34") (pinfunction "KEYPAD_4_P$34") (pintype "bidirectional"))
    )
    (net (code "138") (name "unconnected-(U3-KEYSENSE_N0-PadP$28)") (class "Default")
      (node (ref "U3") (pin "P$28") (pinfunction "KEYSENSE_N0_P$28") (pintype "bidirectional"))
    )
    (net (code "139") (name "unconnected-(U3-KEYSENSE_N1-PadP$27)") (class "Default")
      (node (ref "U3") (pin "P$27") (pinfunction "KEYSENSE_N1_P$27") (pintype "bidirectional"))
    )
    (net (code "140") (name "unconnected-(U3-KEYSENSE_N2-PadP$31)") (class "Default")
      (node (ref "U3") (pin "P$31") (pinfunction "KEYSENSE_N2_P$31") (pintype "bidirectional"))
    )
    (net (code "141") (name "unconnected-(U3-KEYSENSE_N3-PadP$32)") (class "Default")
      (node (ref "U3") (pin "P$32") (pinfunction "KEYSENSE_N3_P$32") (pintype "bidirectional"))
    )
    (net (code "142") (name "unconnected-(U3-KEYSENSE_N4-PadP$36)") (class "Default")
      (node (ref "U3") (pin "P$36") (pinfunction "KEYSENSE_N4_P$36") (pintype "bidirectional"))
    )
    (net (code "143") (name "unconnected-(U3-MIC1N-PadP$24)") (class "Default")
      (node (ref "U3") (pin "P$24") (pinfunction "MIC1N_P$24") (pintype "bidirectional"))
    )
    (net (code "144") (name "unconnected-(U3-MIC1P-PadP$23)") (class "Default")
      (node (ref "U3") (pin "P$23") (pinfunction "MIC1P_P$23") (pintype "bidirectional"))
    )
    (net (code "145") (name "unconnected-(U3-PCM_CLK-PadP$76)") (class "Default")
      (node (ref "U3") (pin "P$76") (pinfunction "PCM_CLK_P$76") (pintype "bidirectional"))
    )
    (net (code "146") (name "unconnected-(U3-PCM_DIN-PadP$74)") (class "Default")
      (node (ref "U3") (pin "P$74") (pinfunction "PCM_DIN_P$74") (pintype "bidirectional"))
    )
    (net (code "147") (name "unconnected-(U3-PCM_DOUT-PadP$73)") (class "Default")
      (node (ref "U3") (pin "P$73") (pinfunction "PCM_DOUT_P$73") (pintype "bidirectional"))
    )
    (net (code "148") (name "unconnected-(U3-PCM_SYNC-PadP$75)") (class "Default")
      (node (ref "U3") (pin "P$75") (pinfunction "PCM_SYNC_P$75") (pintype "bidirectional"))
    )
    (net (code "149") (name "unconnected-(U3-RESERVED_1-PadP$15)") (class "Default")
      (node (ref "U3") (pin "P$15") (pinfunction "RESERVED_1_P$15") (pintype "bidirectional"))
    )
    (net (code "150") (name "unconnected-(U3-RESERVED_2-PadP$16)") (class "Default")
      (node (ref "U3") (pin "P$16") (pinfunction "RESERVED_2_P$16") (pintype "bidirectional"))
    )
    (net (code "151") (name "unconnected-(U3-RESET-PadP$4)") (class "Default")
      (node (ref "U3") (pin "P$4") (pinfunction "RESET_P$4") (pintype "bidirectional"))
    )
    (net (code "152") (name "unconnected-(U3-SPI_CLK-PadP$6)") (class "Default")
      (node (ref "U3") (pin "P$6") (pinfunction "SPI_CLK_P$6") (pintype "bidirectional"))
    )
    (net (code "153") (name "unconnected-(U3-SPI_CS_N-PadP$9)") (class "Default")
      (node (ref "U3") (pin "P$9") (pinfunction "SPI_CS_N_P$9") (pintype "bidirectional"))
    )
    (net (code "154") (name "unconnected-(U3-SPI_MISO_DATA-PadP$7)") (class "Default")
      (node (ref "U3") (pin "P$7") (pinfunction "SPI_MISO_DATA_P$7") (pintype "bidirectional"))
    )
    (net (code "155") (name "unconnected-(U3-SPI_MOSI_DATA-PadP$8)") (class "Default")
      (node (ref "U3") (pin "P$8") (pinfunction "SPI_MOSI_DATA_P$8") (pintype "bidirectional"))
    )
    (net (code "156") (name "unconnected-(U3-SPK_M-PadP$21)") (class "Default")
      (node (ref "U3") (pin "P$21") (pinfunction "SPK_M_P$21") (pintype "bidirectional"))
    )
    (net (code "157") (name "unconnected-(U3-SPK_P-PadP$22)") (class "Default")
      (node (ref "U3") (pin "P$22") (pinfunction "SPK_P_P$22") (pintype "bidirectional"))
    )
    (net (code "158") (name "unconnected-(U3-UART_DCD-PadP$70)") (class "Default")
      (node (ref "U3") (pin "P$70") (pinfunction "UART_DCD_P$70") (pintype "bidirectional"))
    )
    (net (code "159") (name "unconnected-(U3-UART_RI-PadP$69)") (class "Default")
      (node (ref "U3") (pin "P$69") (pinfunction "UART_RI_P$69") (pintype "bidirectional"))
    )
    (net (code "160") (name "unconnected-(U3-USB_DM-PadP$12)") (class "Default")
      (node (ref "U3") (pin "P$12") (pinfunction "USB_DM_P$12") (pintype "bidirectional"))
    )
    (net (code "161") (name "unconnected-(U3-USB_DP-PadP$13)") (class "Default")
      (node (ref "U3") (pin "P$13") (pinfunction "USB_DP_P$13") (pintype "bidirectional"))
    )
    (net (code "162") (name "unconnected-(U3-USB_VBUS-PadP$11)") (class "Default")
      (node (ref "U3") (pin "P$11") (pinfunction "USB_VBUS_P$11") (pintype "bidirectional"))
    )
    (net (code "163") (name "unconnected-(U3-VREG_AUX-PadP$44)") (class "Default")
      (node (ref "U3") (pin "P$44") (pinfunction "VREG_AUX_P$44") (pintype "bidirectional"))
    )
    (net (code "164") (name "unconnected-(U3-VRTC-PadP$42)") (class "Default")
      (node (ref "U3") (pin "P$42") (pinfunction "VRTC_P$42") (pintype "bidirectional"))
    )
  )
)
